# Motherboard_STM32F405RG_r1.net
KiCad netlist of a schematic drawn in EAGLE
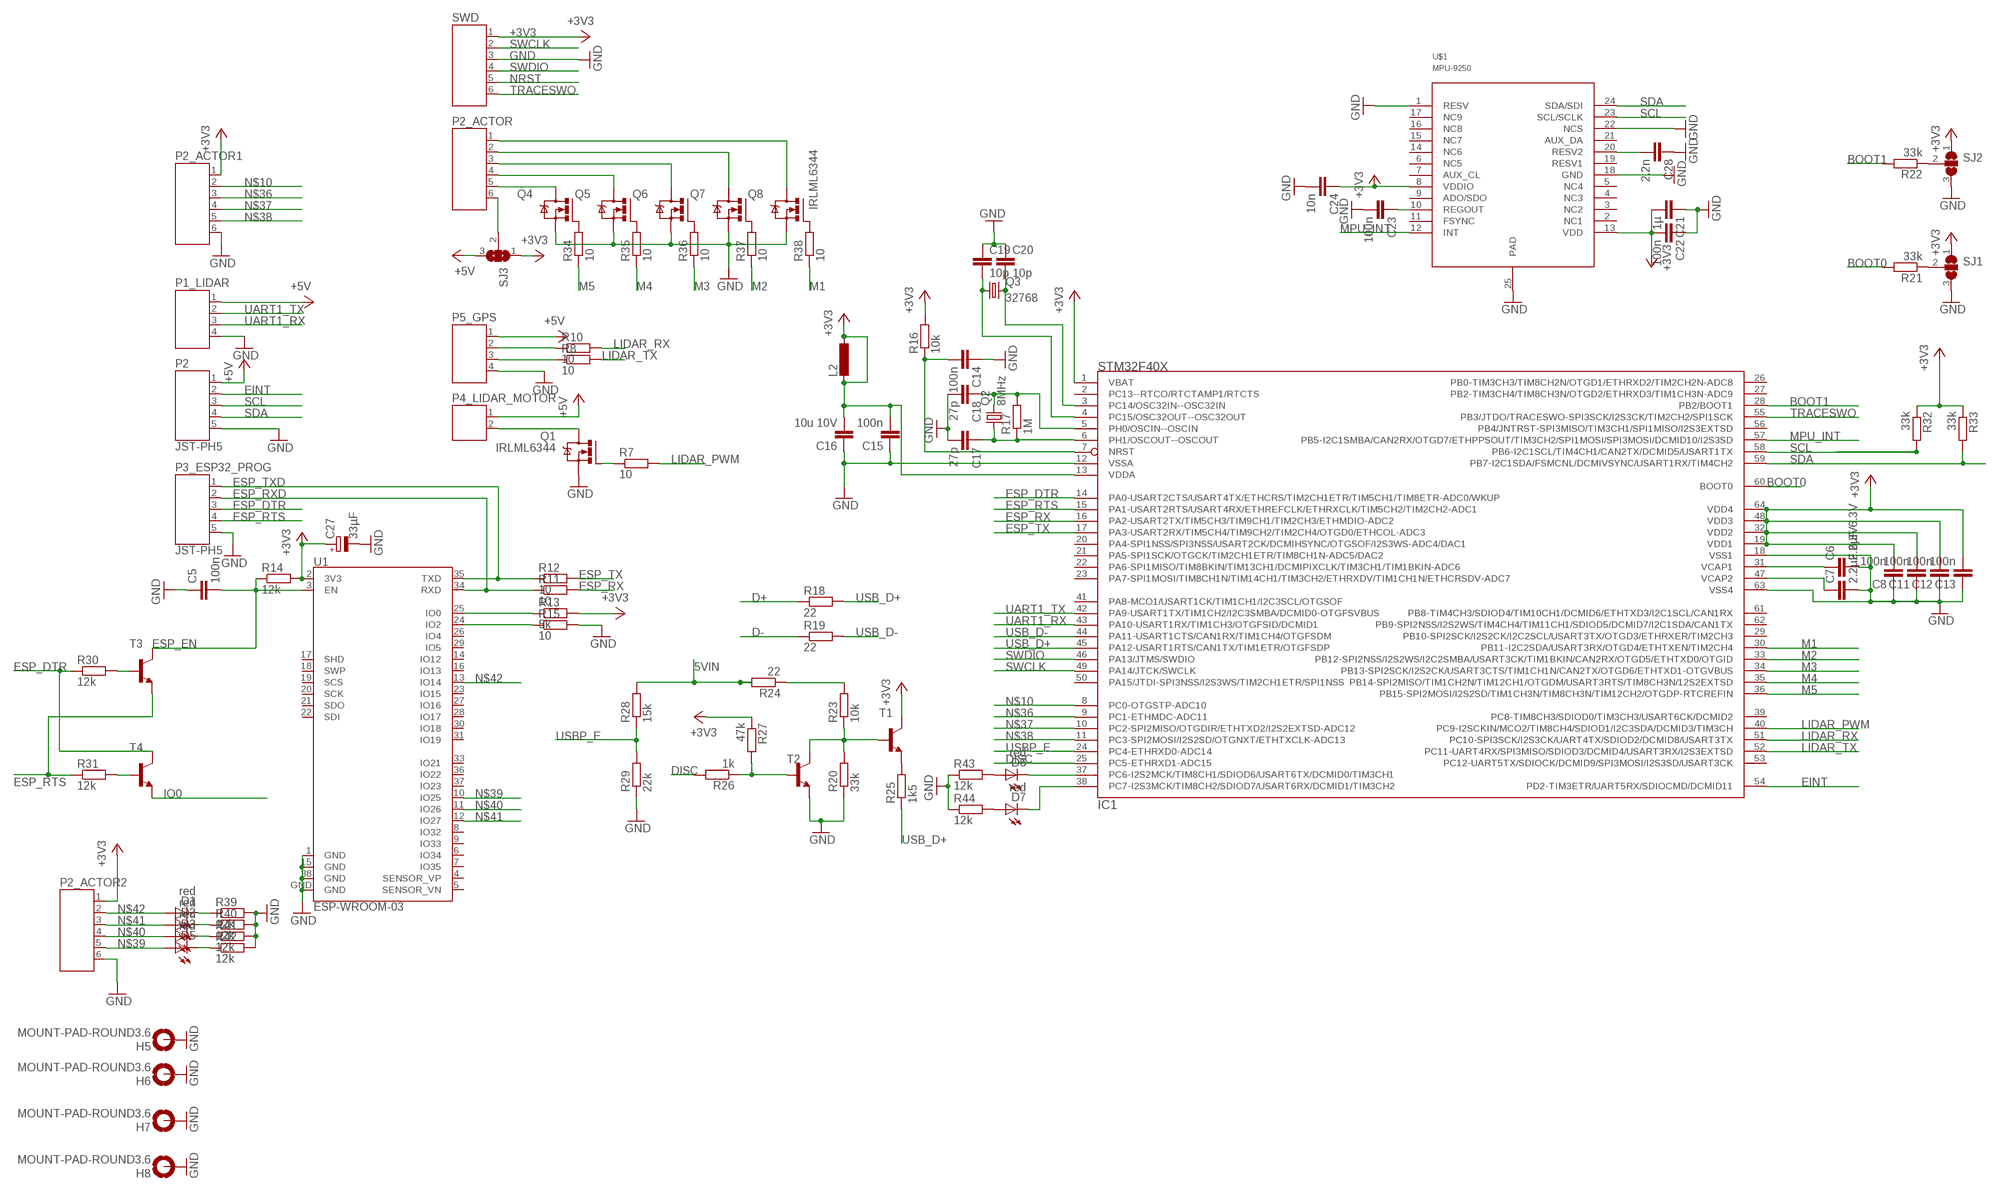
[diagram p0: schematic, sheet 1]
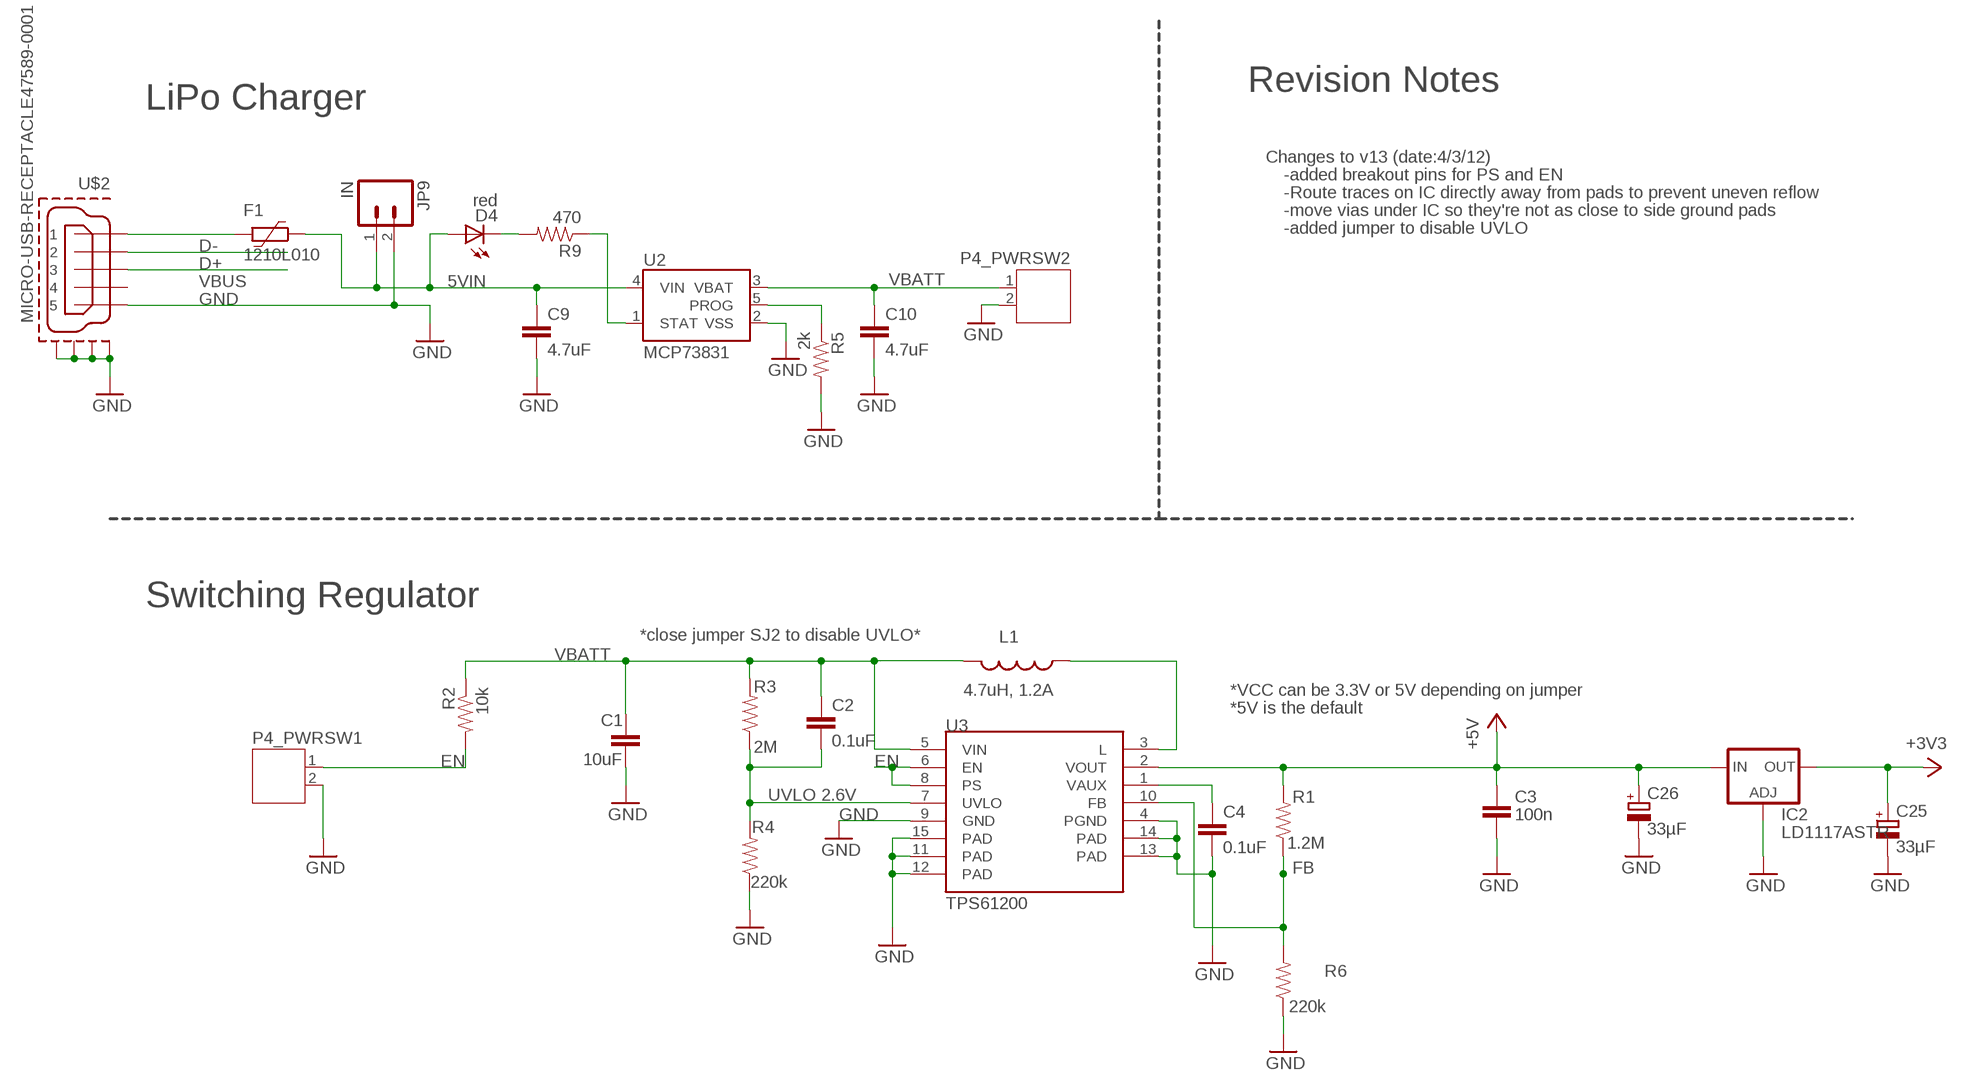
[diagram p1: schematic, sheet 2]

(export (version "E")
  (design (tool "Eeschema 10.0.6"))
  (components
    (comp (ref "C1")
      (value "10uF")
      (footprint "eagle-import:1206")
      (fields (field (name "MF") "KEMET") (field (name "MPN") "C1206C106K8RACTU"))
      (libsource (lib "eagle-import") (part "CAP1206"))
    )
    (comp (ref "C2")
      (value "0.1uF")
      (footprint "eagle-import:0603-CAP")
      (fields (field (name "MF") "YAGEO (PHYCOMP)") (field (name "MPN") "CC0603MRY5V9BB104"))
      (libsource (lib "eagle-import") (part "CAP0603-CAP"))
    )
    (comp (ref "C3")
      (value "100n")
      (footprint "eagle-import:0805")
      (fields (field (name "MF") "KEMET") (field (name "MPN") "C0603C104K5RACTU"))
      (libsource (lib "eagle-import") (part "CAP0805"))
    )
    (comp (ref "C4")
      (value "0.1uF")
      (footprint "eagle-import:0603-CAP")
      (fields (field (name "MF") "YAGEO (PHYCOMP)") (field (name "MPN") "CC0603MRY5V9BB104"))
      (libsource (lib "eagle-import") (part "CAP0603-CAP"))
    )
    (comp (ref "C9")
      (value "4.7uF")
      (footprint "eagle-import:0603-CAP")
      (fields (field (name "MF") "KEMET") (field (name "MPN") "C0603C475K8PACTU"))
      (libsource (lib "eagle-import") (part "CAP0603-CAP"))
    )
    (comp (ref "C10")
      (value "4.7uF")
      (footprint "eagle-import:0603-CAP")
      (fields (field (name "MF") "KEMET") (field (name "MPN") "C0603C475K8PACTU"))
      (libsource (lib "eagle-import") (part "CAP0603-CAP"))
    )
    (comp (ref "C25")
      (value "33µF")
      (footprint "eagle-import:A_3216-18W")
      (fields (field (name "MF") "AVX") (field (name "MPN") "TPSA336M006R0600"))
      (libsource (lib "eagle-import") (part "CPOL-EUA/3216-18W"))
    )
    (comp (ref "C26")
      (value "33µF")
      (footprint "eagle-import:A_3216-18W")
      (fields (field (name "MF") "AVX") (field (name "MPN") "TPSA336M006R0600"))
      (libsource (lib "eagle-import") (part "CPOL-EUA/3216-18W"))
    )
    (comp (ref "D4")
      (value "red")
      (footprint "eagle-import:LED-0603")
      (fields (field (name "MF") "OSRAM") (field (name "MPN") "LSQ976-Z"))
      (libsource (lib "eagle-import") (part "LED0603"))
    )
    (comp (ref "F1")
      (value "1210L010")
      (footprint "eagle-import:1210L")
      (fields
        (field (name "MF") "Littelfuse")
        (field (name "MF_1") "LITTELFUSE")
        (field (name "MPN") "1210L010WR")
      )
      (libsource (lib "eagle-import") (part "?1210L010"))
    )
    (comp (ref "IC2")
      (value "LD1117ASTR")
      (footprint "eagle-import:SOT223")
      (fields (field (name "MF") "ON SEMICONDUCTOR") (field (name "MPN") "NCP1117ST33T3G"))
      (libsource (lib "eagle-import") (part "LD117A?STR"))
    )
    (comp (ref "JP9")
      (value "IN")
      (footprint "eagle-import:1X02")
      (fields
        (field (name "MF") "JST (JAPAN SOLDERLESS TERMINALS)")
        (field (name "MPN") "B2B-PH-K-S(LF)(SN)")
      )
      (libsource (lib "eagle-import") (part "M02PTH"))
    )
    (comp (ref "L1")
      (value "4.7uH, 1.2A")
      (footprint "eagle-import:CDRH2D09")
      (fields (field (name "MF") "MURATA") (field (name "MPN") "LQH3NPN4R7MJ0L"))
      (libsource (lib "eagle-import") (part "INDUCTOR."))
    )
    (comp (ref "P4_PWRSW1")
      (value "JST-PH2")
      (footprint "eagle-import:JST-PH2")
      (fields
        (field (name "MF") "JST (JAPAN SOLDERLESS TERMINALS)")
        (field (name "MPN") "B2B-PH-K-S(LF)(SN)")
      )
      (libsource (lib "eagle-import") (part "JST-PH2"))
    )
    (comp (ref "P4_PWRSW2")
      (value "JST-PH2")
      (footprint "eagle-import:JST-PH2")
      (fields
        (field (name "MF") "JST (JAPAN SOLDERLESS TERMINALS)")
        (field (name "MPN") "B2B-PH-K-S(LF)(SN)")
      )
      (libsource (lib "eagle-import") (part "JST-PH2"))
    )
    (comp (ref "R1")
      (value "1.2M")
      (footprint "eagle-import:0603-RES")
      (fields (field (name "MF") "MULTICOMP") (field (name "MPN") "MCMR06W2004FTL"))
      (libsource (lib "eagle-import") (part "RESISTOR0603-RES"))
    )
    (comp (ref "R2")
      (value "10k")
      (footprint "eagle-import:0603-RES")
      (fields (field (name "MF") "MULTICOMP") (field (name "MPN") "MCMR06X1002FTL"))
      (libsource (lib "eagle-import") (part "RESISTOR0603-RES"))
    )
    (comp (ref "R3")
      (value "2M")
      (footprint "eagle-import:0603-RES")
      (fields (field (name "MF") "KOA SPEER ELECTRONICS") (field (name "MPN") "RK73H1JTTD1204F"))
      (libsource (lib "eagle-import") (part "RESISTOR0603-RES"))
    )
    (comp (ref "R4")
      (value "220k")
      (footprint "eagle-import:0603-RES")
      (fields (field (name "MF") "MULTICOMP") (field (name "MPN") "MCHP03W8F2203T5E"))
      (libsource (lib "eagle-import") (part "RESISTOR0603-RES"))
    )
    (comp (ref "R5")
      (value "2k")
      (footprint "eagle-import:0603-RES")
      (fields (field (name "MF") "YAGEO (PHYCOMP)") (field (name "MPN") "RC0603FR-072K2L."))
      (libsource (lib "eagle-import") (part "RESISTOR0603-RES"))
    )
    (comp (ref "R6")
      (value "220k")
      (footprint "eagle-import:0603-RES")
      (fields (field (name "MF") "MULTICOMP") (field (name "MPN") "MCHP03W8F2203T5E"))
      (libsource (lib "eagle-import") (part "RESISTOR0603-RES"))
    )
    (comp (ref "R9")
      (value "470")
      (footprint "eagle-import:0603-RES")
      (fields (field (name "MF") "MULTICOMP") (field (name "MPN") "MCHP03W8F4700T5E"))
      (libsource (lib "eagle-import") (part "RESISTOR0603-RES"))
    )
    (comp (ref "U$2")
      (value "MICRO-USB-RECEPTACLE47589-0001")
      (footprint "eagle-import:47589-0001")
      (fields (field (name "MF") "MOLEX") (field (name "MPN") "47589-0001"))
      (libsource (lib "eagle-import") (part "MICRO-USB-RECEPTACLE47589-0001"))
    )
    (comp (ref "U2")
      (value "MCP73831")
      (footprint "eagle-import:SOT23-5")
      (fields (field (name "MF") "MICROCHIP") (field (name "MPN") "MCP73831T-2ACI/OT"))
      (libsource (lib "eagle-import") (part "MCP73831"))
    )
    (comp (ref "U3")
      (value "TPS61200")
      (footprint "eagle-import:QFN-10_PAD")
      (fields (field (name "MF") "TEXAS INSTRUMENTS") (field (name "MPN") "TPS61200DRCT"))
      (libsource (lib "eagle-import") (part "TPS61200"))
    )
    (comp (ref "C5")
      (value "100n")
      (footprint "eagle-import:C0603")
      (fields (field (name "MF") "KEMET") (field (name "MPN") "C0603C104K5RACTU"))
      (libsource (lib "eagle-import") (part "C-EUC0603"))
    )
    (comp (ref "C6")
      (value "2.2µF 6.3V")
      (footprint "eagle-import:C0603")
      (fields (field (name "MF") "KEMET") (field (name "MPN") "C0603C225K9PACTU"))
      (libsource (lib "eagle-import") (part "C-EUC0603"))
    )
    (comp (ref "C7")
      (value "2.2µF 6.3V")
      (footprint "eagle-import:C0603")
      (fields (field (name "MF") "KEMET") (field (name "MPN") "C0603C225K9PACTU"))
      (libsource (lib "eagle-import") (part "C-EUC0603"))
    )
    (comp (ref "C8")
      (value "100n")
      (footprint "eagle-import:C0603")
      (fields (field (name "MF") "KEMET") (field (name "MPN") "C0603C104K5RACTU"))
      (libsource (lib "eagle-import") (part "C-EUC0603"))
    )
    (comp (ref "C11")
      (value "100n")
      (footprint "eagle-import:C0603")
      (fields (field (name "MF") "KEMET") (field (name "MPN") "C0603C104K5RACTU"))
      (libsource (lib "eagle-import") (part "C-EUC0603"))
    )
    (comp (ref "C12")
      (value "100n")
      (footprint "eagle-import:C0603")
      (fields (field (name "MF") "KEMET") (field (name "MPN") "C0603C104K5RACTU"))
      (libsource (lib "eagle-import") (part "C-EUC0603"))
    )
    (comp (ref "C13")
      (value "100n")
      (footprint "eagle-import:C0603")
      (fields (field (name "MF") "KEMET") (field (name "MPN") "C0603C104K5RACTU"))
      (libsource (lib "eagle-import") (part "C-EUC0603"))
    )
    (comp (ref "C14")
      (value "100n")
      (footprint "eagle-import:C0603")
      (fields (field (name "MF") "KEMET") (field (name "MPN") "C0603C104K5RACTU"))
      (libsource (lib "eagle-import") (part "C-EUC0603"))
    )
    (comp (ref "C15")
      (value "100n")
      (footprint "eagle-import:C0603")
      (fields (field (name "MF") "KEMET") (field (name "MPN") "C0603C104K5RACTU"))
      (libsource (lib "eagle-import") (part "C-EUC0603"))
    )
    (comp (ref "C16")
      (value "10u 10V")
      (footprint "eagle-import:C1206")
      (fields (field (name "MF") "KEMET") (field (name "MPN") "C1206C106K8RACTU"))
      (libsource (lib "eagle-import") (part "C-EUC1206"))
    )
    (comp (ref "C17")
      (value "27p")
      (footprint "eagle-import:C0603")
      (fields (field (name "MF") "YAGEO (PHYCOMP)") (field (name "MPN") "CC0603JRNPO9BN270"))
      (libsource (lib "eagle-import") (part "C-EUC0603"))
    )
    (comp (ref "C18")
      (value "27p")
      (footprint "eagle-import:C0603")
      (fields (field (name "MF") "YAGEO (PHYCOMP)") (field (name "MPN") "CC0603JRNPO9BN270"))
      (libsource (lib "eagle-import") (part "C-EUC0603"))
    )
    (comp (ref "C19")
      (value "10p")
      (footprint "eagle-import:C0603")
      (fields (field (name "MF") "AVX") (field (name "MPN") "06035A102JAT2A"))
      (libsource (lib "eagle-import") (part "C-EUC0603"))
    )
    (comp (ref "C20")
      (value "10p")
      (footprint "eagle-import:C0603")
      (fields (field (name "MF") "AVX") (field (name "MPN") "06035A102JAT2A"))
      (libsource (lib "eagle-import") (part "C-EUC0603"))
    )
    (comp (ref "C21")
      (value "1µ")
      (footprint "eagle-import:C0603")
      (fields (field (name "MF") "AVX") (field (name "MPN") "0603YC105KAT2A"))
      (libsource (lib "eagle-import") (part "C-EUC0603"))
    )
    (comp (ref "C22")
      (value "100n")
      (footprint "eagle-import:C0603")
      (fields (field (name "MF") "KEMET") (field (name "MPN") "C0603C104K5RACTU"))
      (libsource (lib "eagle-import") (part "C-EUC0603"))
    )
    (comp (ref "C23")
      (value "100n")
      (footprint "eagle-import:C0603")
      (fields (field (name "MF") "KEMET") (field (name "MPN") "C0603C104K5RACTU"))
      (libsource (lib "eagle-import") (part "C-EUC0603"))
    )
    (comp (ref "C24")
      (value "10n")
      (footprint "eagle-import:C0603")
      (fields (field (name "MF") "YAGEO (PHYCOMP)") (field (name "MPN") "CC0603KRX7R9BB103"))
      (libsource (lib "eagle-import") (part "C-EUC0603"))
    )
    (comp (ref "C27")
      (value "33µF")
      (footprint "eagle-import:A_3216-18W")
      (fields (field (name "MF") "AVX") (field (name "MPN") "TPSA336M006R0600"))
      (libsource (lib "eagle-import") (part "CPOL-EUA/3216-18W"))
    )
    (comp (ref "C28")
      (value "2.2n")
      (footprint "eagle-import:C0603")
      (fields (field (name "MF") "YAGEO (PHYCOMP)") (field (name "MPN") "CC0603KRX7R9BB222"))
      (libsource (lib "eagle-import") (part "C-EUC0603"))
    )
    (comp (ref "D1")
      (value "red")
      (footprint "eagle-import:LED-0603")
      (fields (field (name "MF") "OSRAM") (field (name "MPN") "LSQ976-Z"))
      (libsource (lib "eagle-import") (part "LED0603"))
    )
    (comp (ref "D2")
      (value "red")
      (footprint "eagle-import:LED-0603")
      (fields (field (name "MF") "OSRAM") (field (name "MPN") "LSQ976-Z"))
      (libsource (lib "eagle-import") (part "LED0603"))
    )
    (comp (ref "D3")
      (value "red")
      (footprint "eagle-import:LED-0603")
      (fields (field (name "MF") "OSRAM") (field (name "MPN") "LSQ976-Z"))
      (libsource (lib "eagle-import") (part "LED0603"))
    )
    (comp (ref "D5")
      (value "red")
      (footprint "eagle-import:LED-0603")
      (fields (field (name "MF") "OSRAM") (field (name "MPN") "LSQ976-Z"))
      (libsource (lib "eagle-import") (part "LED0603"))
    )
    (comp (ref "D6")
      (value "red")
      (footprint "eagle-import:LED-0603")
      (fields (field (name "MF") "OSRAM") (field (name "MPN") "LSQ976-Z"))
      (libsource (lib "eagle-import") (part "LED0603"))
    )
    (comp (ref "D7")
      (value "red")
      (footprint "eagle-import:LED-0603")
      (fields (field (name "MF") "OSRAM") (field (name "MPN") "LSQ976-Z"))
      (libsource (lib "eagle-import") (part "LED0603"))
    )
    (comp (ref "H5")
      (value "MOUNT-PAD-ROUND3.6")
      (footprint "eagle-import:3,6-PAD")
      (libsource (lib "eagle-import") (part "MOUNT-PAD-ROUND3.6"))
    )
    (comp (ref "H6")
      (value "MOUNT-PAD-ROUND3.6")
      (footprint "eagle-import:3,6-PAD")
      (libsource (lib "eagle-import") (part "MOUNT-PAD-ROUND3.6"))
    )
    (comp (ref "H7")
      (value "MOUNT-PAD-ROUND3.6")
      (footprint "eagle-import:3,6-PAD")
      (libsource (lib "eagle-import") (part "MOUNT-PAD-ROUND3.6"))
    )
    (comp (ref "H8")
      (value "MOUNT-PAD-ROUND3.6")
      (footprint "eagle-import:3,6-PAD")
      (libsource (lib "eagle-import") (part "MOUNT-PAD-ROUND3.6"))
    )
    (comp (ref "IC1")
      (value "STM32F40X")
      (footprint "eagle-import:LQFP64")
      (fields (field (name "MF") "STMICROELECTRONICS") (field (name "MPN") "STM32F405RGT6"))
      (libsource (lib "eagle-import") (part "STM32F40X"))
    )
    (comp (ref "L2")
      (value "L-EUL1812")
      (footprint "eagle-import:L1812")
      (libsource (lib "eagle-import") (part "L-EUL1812"))
    )
    (comp (ref "P1_LIDAR")
      (value "JST-PH4")
      (footprint "eagle-import:JST-PH4")
      (fields
        (field (name "MF") "JST (JAPAN SOLDERLESS TERMINALS)")
        (field (name "MPN") "B4B-PH-K-S(LF)(SN)")
      )
      (libsource (lib "eagle-import") (part "JST-PH4"))
    )
    (comp (ref "P2")
      (value "JST-PH5")
      (footprint "eagle-import:JST-PH5")
      (fields
        (field (name "MF") "JST (JAPAN SOLDERLESS TERMINALS)")
        (field (name "MPN") "B5B-PH-K-S(LF)(SN)")
      )
      (libsource (lib "eagle-import") (part "JST-PH5"))
    )
    (comp (ref "P2_ACTOR")
      (value "JST-PH6")
      (footprint "eagle-import:JST-PH6")
      (fields
        (field (name "MF") "JST (JAPAN SOLDERLESS TERMINALS)")
        (field (name "MPN") "B6B-PH-K-S(LF)(SN)")
      )
      (libsource (lib "eagle-import") (part "JST-PH6"))
    )
    (comp (ref "P2_ACTOR1")
      (value "JST-PH6")
      (footprint "eagle-import:JST-PH6")
      (fields
        (field (name "MF") "JST (JAPAN SOLDERLESS TERMINALS)")
        (field (name "MPN") "B6B-PH-K-S(LF)(SN)")
      )
      (libsource (lib "eagle-import") (part "JST-PH6"))
    )
    (comp (ref "P2_ACTOR2")
      (value "JST-PH6")
      (footprint "eagle-import:JST-PH6")
      (fields
        (field (name "MF") "JST (JAPAN SOLDERLESS TERMINALS)")
        (field (name "MPN") "B6B-PH-K-S(LF)(SN)")
      )
      (libsource (lib "eagle-import") (part "JST-PH6"))
    )
    (comp (ref "P3_ESP32_PROG")
      (value "JST-PH5")
      (footprint "eagle-import:JST-PH5")
      (fields
        (field (name "MF") "JST (JAPAN SOLDERLESS TERMINALS)")
        (field (name "MPN") "B5B-PH-K-S(LF)(SN)")
      )
      (libsource (lib "eagle-import") (part "JST-PH5"))
    )
    (comp (ref "P4_LIDAR_MOTOR")
      (value "JST-PH2")
      (footprint "eagle-import:JST-PH2")
      (fields
        (field (name "MF") "JST (JAPAN SOLDERLESS TERMINALS)")
        (field (name "MPN") "B2B-PH-K-S(LF)(SN)")
      )
      (libsource (lib "eagle-import") (part "JST-PH2"))
    )
    (comp (ref "P5_GPS")
      (value "JST-PH4")
      (footprint "eagle-import:JST-PH4")
      (fields
        (field (name "MF") "JST (JAPAN SOLDERLESS TERMINALS)")
        (field (name "MPN") "B4B-PH-K-S(LF)(SN)")
      )
      (libsource (lib "eagle-import") (part "JST-PH4"))
    )
    (comp (ref "Q1")
      (value "IRLML6344")
      (footprint "eagle-import:SOT23")
      (fields (field (name "MF") "INFINEON") (field (name "MPN") "IRLML6344TRPBF"))
      (libsource (lib "eagle-import") (part "IRLML6344"))
    )
    (comp (ref "Q2")
      (value "8MHz")
      (footprint "eagle-import:HC18U-V")
      (fields
        (field (name "MF") "MULTICOMP")
        (field (name "MPN") "HC49S-8-30-50-70-30-ATF")
        (field (name "OC_FARNELL") "1666997")
      )
      (libsource (lib "eagle-import") (part "CRYSTALHC18U-V"))
    )
    (comp (ref "Q3")
      (value "32768")
      (footprint "eagle-import:TC38H")
      (fields
        (field (name "MF") "CITIZEN FINETECH MIYOTA")
        (field (name "MPN") "CFS206 32.768KDZB-UB")
        (field (name "OC_FARNELL") "1457085")
      )
      (libsource (lib "eagle-import") (part "CRYSTALTC38H"))
    )
    (comp (ref "Q4")
      (value "IRLML6344")
      (footprint "eagle-import:SOT23")
      (fields (field (name "MF") "INFINEON") (field (name "MPN") "IRLML6344TRPBF"))
      (libsource (lib "eagle-import") (part "IRLML6344"))
    )
    (comp (ref "Q5")
      (value "IRLML6344")
      (footprint "eagle-import:SOT23")
      (fields (field (name "MF") "INFINEON") (field (name "MPN") "IRLML6344TRPBF"))
      (libsource (lib "eagle-import") (part "IRLML6344"))
    )
    (comp (ref "Q6")
      (value "IRLML6344")
      (footprint "eagle-import:SOT23")
      (fields (field (name "MF") "INFINEON") (field (name "MPN") "IRLML6344TRPBF"))
      (libsource (lib "eagle-import") (part "IRLML6344"))
    )
    (comp (ref "Q7")
      (value "IRLML6344")
      (footprint "eagle-import:SOT23")
      (fields (field (name "MF") "INFINEON") (field (name "MPN") "IRLML6344TRPBF"))
      (libsource (lib "eagle-import") (part "IRLML6344"))
    )
    (comp (ref "Q8")
      (value "IRLML6344")
      (footprint "eagle-import:SOT23")
      (fields (field (name "MF") "INFINEON") (field (name "MPN") "IRLML6344TRPBF"))
      (libsource (lib "eagle-import") (part "IRLML6344"))
    )
    (comp (ref "R7")
      (value "10")
      (footprint "eagle-import:R0603")
      (fields (field (name "MF") "VISHAY") (field (name "MPN") "CRCW060310R0FKEA"))
      (libsource (lib "eagle-import") (part "R-EU_R0603"))
    )
    (comp (ref "R8")
      (value "10")
      (footprint "eagle-import:R0603")
      (fields (field (name "MF") "VISHAY") (field (name "MPN") "CRCW060310R0FKEA"))
      (libsource (lib "eagle-import") (part "R-EU_R0603"))
    )
    (comp (ref "R10")
      (value "10")
      (footprint "eagle-import:R0603")
      (fields (field (name "MF") "VISHAY") (field (name "MPN") "CRCW060310R0FKEA"))
      (libsource (lib "eagle-import") (part "R-EU_R0603"))
    )
    (comp (ref "R11")
      (value "10")
      (footprint "eagle-import:R0603")
      (fields (field (name "MF") "VISHAY") (field (name "MPN") "CRCW060310R0FKEA"))
      (libsource (lib "eagle-import") (part "R-EU_R0603"))
    )
    (comp (ref "R12")
      (value "10")
      (footprint "eagle-import:R0603")
      (fields (field (name "MF") "VISHAY") (field (name "MPN") "CRCW060310R0FKEA"))
      (libsource (lib "eagle-import") (part "R-EU_R0603"))
    )
    (comp (ref "R13")
      (value "5k")
      (footprint "eagle-import:R0603")
      (fields (field (name "MF") "VISHAY") (field (name "MPN") "CRCW060310R0FKEA"))
      (libsource (lib "eagle-import") (part "R-EU_R0603"))
    )
    (comp (ref "R14")
      (value "12k")
      (footprint "eagle-import:R0603")
      (fields (field (name "MF") "VISHAY") (field (name "MPN") "CRCW060310R0FKEA"))
      (libsource (lib "eagle-import") (part "R-EU_R0603"))
    )
    (comp (ref "R15")
      (value "10")
      (footprint "eagle-import:R0603")
      (fields (field (name "MF") "VISHAY") (field (name "MPN") "CRCW060310R0FKEA"))
      (libsource (lib "eagle-import") (part "R-EU_R0603"))
    )
    (comp (ref "R16")
      (value "10k")
      (footprint "eagle-import:R0603")
      (fields (field (name "MF") "VISHAY") (field (name "MPN") "CRCW060310R0FKEA"))
      (libsource (lib "eagle-import") (part "R-EU_R0603"))
    )
    (comp (ref "R17")
      (value "1M")
      (footprint "eagle-import:R0603")
      (fields (field (name "MF") "VISHAY") (field (name "MPN") "CRCW06031M00FKEA"))
      (libsource (lib "eagle-import") (part "R-EU_R0603"))
    )
    (comp (ref "R18")
      (value "22")
      (footprint "eagle-import:R0603")
      (fields (field (name "MF") "VISHAY") (field (name "MPN") "CRCW060322R0FKEA"))
      (libsource (lib "eagle-import") (part "R-EU_R0603"))
    )
    (comp (ref "R19")
      (value "22")
      (footprint "eagle-import:R0603")
      (fields (field (name "MF") "VISHAY") (field (name "MPN") "CRCW060322R0FKEA"))
      (libsource (lib "eagle-import") (part "R-EU_R0603"))
    )
    (comp (ref "R20")
      (value "33k")
      (footprint "eagle-import:R0603")
      (fields (field (name "MF") "VISHAY") (field (name "MPN") "CRCW060333K0FKEA"))
      (libsource (lib "eagle-import") (part "R-EU_R0603"))
    )
    (comp (ref "R21")
      (value "33k")
      (footprint "eagle-import:R0603")
      (fields (field (name "MF") "VISHAY") (field (name "MPN") "CRCW060333K0FKEA"))
      (libsource (lib "eagle-import") (part "R-EU_R0603"))
    )
    (comp (ref "R22")
      (value "33k")
      (footprint "eagle-import:R0603")
      (fields (field (name "MF") "VISHAY") (field (name "MPN") "CRCW060333K0FKEA"))
      (libsource (lib "eagle-import") (part "R-EU_R0603"))
    )
    (comp (ref "R23")
      (value "10k")
      (footprint "eagle-import:R0603")
      (fields (field (name "MF") "MULTICOMP") (field (name "MPN") "MCMR06X1002FTL"))
      (libsource (lib "eagle-import") (part "R-EU_R0603"))
    )
    (comp (ref "R24")
      (value "22")
      (footprint "eagle-import:R0603")
      (fields (field (name "MF") "VISHAY") (field (name "MPN") "CRCW060322R0FKEA"))
      (libsource (lib "eagle-import") (part "R-EU_R0603"))
    )
    (comp (ref "R25")
      (value "1k5")
      (footprint "eagle-import:R0603")
      (fields (field (name "MF") "MULTICOMP") (field (name "MPN") "MCMR06X1501FTL"))
      (libsource (lib "eagle-import") (part "R-EU_R0603"))
    )
    (comp (ref "R26")
      (value "1k")
      (footprint "eagle-import:R0603")
      (fields (field (name "MF") "VISHAY") (field (name "MPN") "CRCW06031K00FKEA"))
      (libsource (lib "eagle-import") (part "R-EU_R0603"))
    )
    (comp (ref "R27")
      (value "47k")
      (footprint "eagle-import:R0603")
      (fields (field (name "MF") "VISHAY") (field (name "MPN") "CRCW060347K0FKEA"))
      (libsource (lib "eagle-import") (part "R-EU_R0603"))
    )
    (comp (ref "R28")
      (value "15k")
      (footprint "eagle-import:R0603")
      (fields (field (name "MF") "VISHAY") (field (name "MPN") "CRCW060315K0FKEA"))
      (libsource (lib "eagle-import") (part "R-EU_R0603"))
    )
    (comp (ref "R29")
      (value "22k")
      (footprint "eagle-import:R0603")
      (fields (field (name "MF") "TE CONNECTIVITY / NEOHM") (field (name "MPN") "CPF0603F4K22C1"))
      (libsource (lib "eagle-import") (part "R-EU_R0603"))
    )
    (comp (ref "R30")
      (value "12k")
      (footprint "eagle-import:R0603")
      (fields (field (name "MF") "MULTICOMP") (field (name "MPN") "MC0063W060312K8"))
      (libsource (lib "eagle-import") (part "R-EU_R0603"))
    )
    (comp (ref "R31")
      (value "12k")
      (footprint "eagle-import:R0603")
      (fields (field (name "MF") "MULTICOMP") (field (name "MPN") "MC0063W060312K8"))
      (libsource (lib "eagle-import") (part "R-EU_R0603"))
    )
    (comp (ref "R32")
      (value "33k")
      (footprint "eagle-import:R0603")
      (fields (field (name "MF") "VISHAY") (field (name "MPN") "CRCW060333K0FKEA"))
      (libsource (lib "eagle-import") (part "R-EU_R0603"))
    )
    (comp (ref "R33")
      (value "33k")
      (footprint "eagle-import:R0603")
      (fields (field (name "MF") "VISHAY") (field (name "MPN") "CRCW060333K0FKEA"))
      (libsource (lib "eagle-import") (part "R-EU_R0603"))
    )
    (comp (ref "R34")
      (value "10")
      (footprint "eagle-import:R0603")
      (fields (field (name "MF") "VISHAY") (field (name "MPN") "CRCW060310R0FKEA"))
      (libsource (lib "eagle-import") (part "R-EU_R0603"))
    )
    (comp (ref "R35")
      (value "10")
      (footprint "eagle-import:R0603")
      (fields (field (name "MF") "VISHAY") (field (name "MPN") "CRCW060310R0FKEA"))
      (libsource (lib "eagle-import") (part "R-EU_R0603"))
    )
    (comp (ref "R36")
      (value "10")
      (footprint "eagle-import:R0603")
      (fields (field (name "MF") "VISHAY") (field (name "MPN") "CRCW060310R0FKEA"))
      (libsource (lib "eagle-import") (part "R-EU_R0603"))
    )
    (comp (ref "R37")
      (value "10")
      (footprint "eagle-import:R0603")
      (fields (field (name "MF") "VISHAY") (field (name "MPN") "CRCW060310R0FKEA"))
      (libsource (lib "eagle-import") (part "R-EU_R0603"))
    )
    (comp (ref "R38")
      (value "10")
      (footprint "eagle-import:R0603")
      (fields (field (name "MF") "VISHAY") (field (name "MPN") "CRCW060310R0FKEA"))
      (libsource (lib "eagle-import") (part "R-EU_R0603"))
    )
    (comp (ref "R39")
      (value "12k")
      (footprint "eagle-import:R0603")
      (fields (field (name "MF") "MULTICOMP") (field (name "MPN") "MC0063W060312K8"))
      (libsource (lib "eagle-import") (part "R-EU_R0603"))
    )
    (comp (ref "R40")
      (value "12k")
      (footprint "eagle-import:R0603")
      (fields (field (name "MF") "MULTICOMP") (field (name "MPN") "MC0063W060312K8"))
      (libsource (lib "eagle-import") (part "R-EU_R0603"))
    )
    (comp (ref "R41")
      (value "12k")
      (footprint "eagle-import:R0603")
      (fields (field (name "MF") "MULTICOMP") (field (name "MPN") "MC0063W060312K8"))
      (libsource (lib "eagle-import") (part "R-EU_R0603"))
    )
    (comp (ref "R42")
      (value "12k")
      (footprint "eagle-import:R0603")
      (fields (field (name "MF") "MULTICOMP") (field (name "MPN") "MC0063W060312K8"))
      (libsource (lib "eagle-import") (part "R-EU_R0603"))
    )
    (comp (ref "R43")
      (value "12k")
      (footprint "eagle-import:R0603")
      (fields (field (name "MF") "MULTICOMP") (field (name "MPN") "MC0063W060312K8"))
      (libsource (lib "eagle-import") (part "R-EU_R0603"))
    )
    (comp (ref "R44")
      (value "12k")
      (footprint "eagle-import:R0603")
      (fields (field (name "MF") "MULTICOMP") (field (name "MPN") "MC0063W060312K8"))
      (libsource (lib "eagle-import") (part "R-EU_R0603"))
    )
    (comp (ref "SJ1")
      (value "SJ2W")
      (footprint "eagle-import:SJ_2")
      (libsource (lib "eagle-import") (part "SJ2W"))
    )
    (comp (ref "SJ2")
      (value "SJ2W")
      (footprint "eagle-import:SJ_2")
      (libsource (lib "eagle-import") (part "SJ2W"))
    )
    (comp (ref "SJ3")
      (value "SJ2W")
      (footprint "eagle-import:SJ_2")
      (libsource (lib "eagle-import") (part "SJ2W"))
    )
    (comp (ref "SWD")
      (value "JST-PH6")
      (footprint "eagle-import:JST-PH6")
      (fields
        (field (name "MF") "JST (JAPAN SOLDERLESS TERMINALS)")
        (field (name "MPN") "B6B-PH-K-S(LF)(SN)")
      )
      (libsource (lib "eagle-import") (part "JST-PH6"))
    )
    (comp (ref "T1")
      (value "BC817-16-NPN-SOT23-BEC")
      (footprint "eagle-import:SOT23-BEC")
      (fields (field (name "MF") "NEXPERIA") (field (name "MPN") "BC817,215"))
      (libsource (lib "eagle-import") (part "-NPN-SOT23-BECBC817-16"))
    )
    (comp (ref "T2")
      (value "BC817-16-NPN-SOT23-BEC")
      (footprint "eagle-import:SOT23-BEC")
      (fields (field (name "MF") "NEXPERIA") (field (name "MPN") "BC817,215"))
      (libsource (lib "eagle-import") (part "-NPN-SOT23-BECBC817-16"))
    )
    (comp (ref "T3")
      (value "BC817-16-NPN-SOT23-BEC")
      (footprint "eagle-import:SOT23-BEC")
      (fields (field (name "MF") "NEXPERIA") (field (name "MPN") "BC817,215"))
      (libsource (lib "eagle-import") (part "-NPN-SOT23-BECBC817-16"))
    )
    (comp (ref "T4")
      (value "BC817-16-NPN-SOT23-BEC")
      (footprint "eagle-import:SOT23-BEC")
      (fields (field (name "MF") "NEXPERIA") (field (name "MPN") "BC817,215"))
      (libsource (lib "eagle-import") (part "-NPN-SOT23-BECBC817-16"))
    )
    (comp (ref "U$1")
      (value "MPU-9250")
      (footprint "eagle-import:LEAD-QFN24")
      (fields (field (name "MF") "INVENSENSE") (field (name "MPN") "MPU-6050"))
      (libsource (lib "eagle-import") (part "MPU-9250"))
    )
    (comp (ref "U1")
      (value "ESP-WROOM-03")
      (footprint "eagle-import:ESP-WROOM-03")
      (libsource (lib "eagle-import") (part "ESP-WROOM-03"))
    )
  )
  (nets
    (net (code "1") (name "+3V3") (class "Default")
      (node (ref "C11") (pin "2") (pinfunction "2_2") (pintype "passive"))
      (node (ref "C12") (pin "2") (pinfunction "2_2") (pintype "passive"))
      (node (ref "C13") (pin "2") (pinfunction "2_2") (pintype "passive"))
      (node (ref "C15") (pin "2") (pinfunction "2_2") (pintype "passive"))
      (node (ref "C16") (pin "2") (pinfunction "2_2") (pintype "passive"))
      (node (ref "C21") (pin "2") (pinfunction "2_2") (pintype "passive"))
      (node (ref "C22") (pin "2") (pinfunction "2_2") (pintype "passive"))
      (node (ref "C24") (pin "1") (pinfunction "1_1") (pintype "passive"))
      (node (ref "C25") (pin "+") (pinfunction "+_+") (pintype "passive"))
      (node (ref "C27") (pin "+") (pinfunction "+_+") (pintype "passive"))
      (node (ref "C8") (pin "2") (pinfunction "2_2") (pintype "passive"))
      (node (ref "IC1") (pin "1") (pinfunction "VBAT_1") (pintype "power_in"))
      (node (ref "IC1") (pin "13") (pinfunction "VDDA_13") (pintype "power_in"))
      (node (ref "IC1") (pin "19") (pinfunction "VDD1_19") (pintype "power_in"))
      (node (ref "IC1") (pin "32") (pinfunction "VDD2_32") (pintype "power_in"))
      (node (ref "IC1") (pin "48") (pinfunction "VDD3_48") (pintype "power_in"))
      (node (ref "IC1") (pin "64") (pinfunction "VDD4_64") (pintype "bidirectional"))
      (node (ref "IC2") (pin "2") (pinfunction "OUT_2") (pintype "passive"))
      (node (ref "IC2") (pin "4") (pinfunction "OUT_4") (pintype "passive"))
      (node (ref "L2") (pin "1") (pinfunction "1_1") (pintype "passive"))
      (node (ref "L2") (pin "2") (pinfunction "2_2") (pintype "passive"))
      (node (ref "P2_ACTOR1") (pin "1") (pinfunction "1_1") (pintype "passive"))
      (node (ref "P2_ACTOR2") (pin "1") (pinfunction "1_1") (pintype "passive"))
      (node (ref "R13") (pin "2") (pinfunction "2_2") (pintype "passive"))
      (node (ref "R14") (pin "2") (pinfunction "2_2") (pintype "passive"))
      (node (ref "R16") (pin "2") (pinfunction "2_2") (pintype "passive"))
      (node (ref "R27") (pin "1") (pinfunction "1_1") (pintype "passive"))
      (node (ref "R32") (pin "1") (pinfunction "1_1") (pintype "passive"))
      (node (ref "R33") (pin "1") (pinfunction "1_1") (pintype "passive"))
      (node (ref "SJ1") (pin "1") (pinfunction "1_1") (pintype "passive"))
      (node (ref "SJ2") (pin "1") (pinfunction "1_1") (pintype "passive"))
      (node (ref "SJ3") (pin "1") (pinfunction "1_1") (pintype "passive"))
      (node (ref "SWD") (pin "1") (pinfunction "1_1") (pintype "passive"))
      (node (ref "T1") (pin "C") (pinfunction "C_C") (pintype "passive"))
      (node (ref "U$1") (pin "13") (pinfunction "VDD_13") (pintype "bidirectional"))
      (node (ref "U$1") (pin "8") (pinfunction "VDDIO_8") (pintype "bidirectional"))
      (node (ref "U1") (pin "2") (pinfunction "3V3_2") (pintype "bidirectional"))
    )
    (net (code "2") (name "+5V") (class "Default")
      (node (ref "C26") (pin "+") (pinfunction "+_+") (pintype "passive"))
      (node (ref "C3") (pin "1") (pinfunction "1_1") (pintype "passive"))
      (node (ref "IC2") (pin "3") (pinfunction "IN_3") (pintype "input"))
      (node (ref "P1_LIDAR") (pin "1") (pinfunction "1_1") (pintype "passive"))
      (node (ref "P2") (pin "1") (pinfunction "1_1") (pintype "passive"))
      (node (ref "P4_LIDAR_MOTOR") (pin "1") (pinfunction "1_1") (pintype "passive"))
      (node (ref "P5_GPS") (pin "1") (pinfunction "1_1") (pintype "passive"))
      (node (ref "R1") (pin "2") (pinfunction "2_2") (pintype "passive"))
      (node (ref "SJ3") (pin "3") (pinfunction "3_3") (pintype "passive"))
      (node (ref "U3") (pin "2") (pinfunction "VOUT_2") (pintype "passive"))
    )
    (net (code "3") (name "5VIN") (class "Default")
      (node (ref "C9") (pin "1") (pinfunction "1_1") (pintype "passive"))
      (node (ref "D4") (pin "A") (pinfunction "A_A") (pintype "passive"))
      (node (ref "F1") (pin "1") (pinfunction "1_1") (pintype "passive"))
      (node (ref "JP9") (pin "1") (pinfunction "1_1") (pintype "passive"))
      (node (ref "R24") (pin "2") (pinfunction "2_2") (pintype "passive"))
      (node (ref "R28") (pin "2") (pinfunction "2_2") (pintype "passive"))
      (node (ref "U2") (pin "4") (pinfunction "VIN_4") (pintype "power_in"))
    )
    (net (code "4") (name "BOOT0") (class "Default")
      (node (ref "IC1") (pin "60") (pinfunction "BOOT0_60") (pintype "input"))
      (node (ref "R21") (pin "2") (pinfunction "2_2") (pintype "passive"))
    )
    (net (code "5") (name "BOOT1") (class "Default")
      (node (ref "IC1") (pin "28") (pinfunction "PB2/BOOT1_28") (pintype "bidirectional"))
      (node (ref "R22") (pin "2") (pinfunction "2_2") (pintype "passive"))
    )
    (net (code "6") (name "D+") (class "Default")
      (node (ref "R18") (pin "1") (pinfunction "1_1") (pintype "passive"))
      (node (ref "U$2") (pin "3") (pinfunction "3_3") (pintype "input"))
    )
    (net (code "7") (name "D-") (class "Default")
      (node (ref "R19") (pin "1") (pinfunction "1_1") (pintype "passive"))
      (node (ref "U$2") (pin "2") (pinfunction "2_2") (pintype "input"))
    )
    (net (code "8") (name "DISC") (class "Default")
      (node (ref "IC1") (pin "25") (pinfunction "PC5-ETHRXD1-ADC15_25") (pintype "bidirectional"))
      (node (ref "R26") (pin "2") (pinfunction "2_2") (pintype "passive"))
    )
    (net (code "9") (name "EINT") (class "Default")
      (node (ref "IC1") (pin "54") (pinfunction "PD2-TIM3ETR/UART5RX/SDIOCMD/DCMID11_54") (pintype "bidirectional"))
      (node (ref "P2") (pin "2") (pinfunction "2_2") (pintype "passive"))
    )
    (net (code "10") (name "EN") (class "Default")
      (node (ref "P4_PWRSW1") (pin "1") (pinfunction "1_1") (pintype "passive"))
      (node (ref "R2") (pin "2") (pinfunction "2_2") (pintype "passive"))
      (node (ref "U3") (pin "6") (pinfunction "EN_6") (pintype "input"))
      (node (ref "U3") (pin "8") (pinfunction "PS_8") (pintype "input"))
    )
    (net (code "11") (name "ESP_DTR") (class "Default")
      (node (ref "IC1") (pin "14") (pinfunction "PA0-USART2CTS/USART4TX/ETHCRS/TIM2CH1ETR/TIM5CH1/TIM8ETR-ADC0/WKUP_14") (pintype "bidirectional"))
      (node (ref "P3_ESP32_PROG") (pin "3") (pinfunction "3_3") (pintype "passive"))
      (node (ref "R30") (pin "1") (pinfunction "1_1") (pintype "passive"))
      (node (ref "T4") (pin "C") (pinfunction "C_C") (pintype "passive"))
    )
    (net (code "12") (name "ESP_EN") (class "Default")
      (node (ref "C5") (pin "2") (pinfunction "2_2") (pintype "passive"))
      (node (ref "R14") (pin "1") (pinfunction "1_1") (pintype "passive"))
      (node (ref "T3") (pin "C") (pinfunction "C_C") (pintype "passive"))
      (node (ref "U1") (pin "3") (pinfunction "EN_3") (pintype "bidirectional"))
    )
    (net (code "13") (name "ESP_RTS") (class "Default")
      (node (ref "IC1") (pin "15") (pinfunction "PA1-USART2RTS/USART4RX/ETHREFCLK/ETHRXCLK/TIM5CH2/TIM2CH2-ADC1_15") (pintype "bidirectional"))
      (node (ref "P3_ESP32_PROG") (pin "4") (pinfunction "4_4") (pintype "passive"))
      (node (ref "R31") (pin "1") (pinfunction "1_1") (pintype "passive"))
      (node (ref "T3") (pin "E") (pinfunction "E_E") (pintype "passive"))
    )
    (net (code "14") (name "ESP_RX") (class "Default")
      (node (ref "IC1") (pin "16") (pinfunction "PA2-USART2TX/TIM5CH3/TIM9CH1/TIM2CH3/ETHMDIO-ADC2_16") (pintype "bidirectional"))
      (node (ref "R11") (pin "2") (pinfunction "2_2") (pintype "passive"))
    )
    (net (code "15") (name "ESP_RXD") (class "Default")
      (node (ref "P3_ESP32_PROG") (pin "2") (pinfunction "2_2") (pintype "passive"))
      (node (ref "R11") (pin "1") (pinfunction "1_1") (pintype "passive"))
      (node (ref "U1") (pin "34") (pinfunction "RXD_34") (pintype "bidirectional"))
    )
    (net (code "16") (name "ESP_TX") (class "Default")
      (node (ref "IC1") (pin "17") (pinfunction "PA3-USART2RX/TIM5CH4/TIM9CH2/TIM2CH4/OTGD0/ETHCOL-ADC3_17") (pintype "bidirectional"))
      (node (ref "R12") (pin "2") (pinfunction "2_2") (pintype "passive"))
    )
    (net (code "17") (name "ESP_TXD") (class "Default")
      (node (ref "P3_ESP32_PROG") (pin "1") (pinfunction "1_1") (pintype "passive"))
      (node (ref "R12") (pin "1") (pinfunction "1_1") (pintype "passive"))
      (node (ref "U1") (pin "35") (pinfunction "TXD_35") (pintype "bidirectional"))
    )
    (net (code "18") (name "FB") (class "Default")
      (node (ref "R1") (pin "1") (pinfunction "1_1") (pintype "passive"))
      (node (ref "R6") (pin "2") (pinfunction "2_2") (pintype "passive"))
      (node (ref "U3") (pin "10") (pinfunction "FB_10") (pintype "passive"))
    )
    (net (code "19") (name "GND") (class "Default")
      (node (ref "C1") (pin "2") (pinfunction "2_2") (pintype "passive"))
      (node (ref "C10") (pin "2") (pinfunction "2_2") (pintype "passive"))
      (node (ref "C11") (pin "1") (pinfunction "1_1") (pintype "passive"))
      (node (ref "C12") (pin "1") (pinfunction "1_1") (pintype "passive"))
      (node (ref "C13") (pin "1") (pinfunction "1_1") (pintype "passive"))
      (node (ref "C14") (pin "1") (pinfunction "1_1") (pintype "passive"))
      (node (ref "C15") (pin "1") (pinfunction "1_1") (pintype "passive"))
      (node (ref "C16") (pin "1") (pinfunction "1_1") (pintype "passive"))
      (node (ref "C17") (pin "2") (pinfunction "2_2") (pintype "passive"))
      (node (ref "C18") (pin "2") (pinfunction "2_2") (pintype "passive"))
      (node (ref "C19") (pin "1") (pinfunction "1_1") (pintype "passive"))
      (node (ref "C20") (pin "1") (pinfunction "1_1") (pintype "passive"))
      (node (ref "C21") (pin "1") (pinfunction "1_1") (pintype "passive"))
      (node (ref "C22") (pin "1") (pinfunction "1_1") (pintype "passive"))
      (node (ref "C23") (pin "2") (pinfunction "2_2") (pintype "passive"))
      (node (ref "C24") (pin "2") (pinfunction "2_2") (pintype "passive"))
      (node (ref "C25") (pin "-") (pinfunction "-_-") (pintype "passive"))
      (node (ref "C26") (pin "-") (pinfunction "-_-") (pintype "passive"))
      (node (ref "C27") (pin "-") (pinfunction "-_-") (pintype "passive"))
      (node (ref "C28") (pin "1") (pinfunction "1_1") (pintype "passive"))
      (node (ref "C3") (pin "2") (pinfunction "2_2") (pintype "passive"))
      (node (ref "C4") (pin "2") (pinfunction "2_2") (pintype "passive"))
      (node (ref "C5") (pin "1") (pinfunction "1_1") (pintype "passive"))
      (node (ref "C6") (pin "2") (pinfunction "2_2") (pintype "passive"))
      (node (ref "C7") (pin "2") (pinfunction "2_2") (pintype "passive"))
      (node (ref "C8") (pin "1") (pinfunction "1_1") (pintype "passive"))
      (node (ref "C9") (pin "2") (pinfunction "2_2") (pintype "passive"))
      (node (ref "H5") (pin "B3,6") (pinfunction "MOUNT_B3,6") (pintype "passive"))
      (node (ref "H6") (pin "B3,6") (pinfunction "MOUNT_B3,6") (pintype "passive"))
      (node (ref "H7") (pin "B3,6") (pinfunction "MOUNT_B3,6") (pintype "passive"))
      (node (ref "H8") (pin "B3,6") (pinfunction "MOUNT_B3,6") (pintype "passive"))
      (node (ref "IC1") (pin "12") (pinfunction "VSSA_12") (pintype "power_in"))
      (node (ref "IC1") (pin "18") (pinfunction "VSS1_18") (pintype "power_in"))
      (node (ref "IC1") (pin "63") (pinfunction "VSS4_63") (pintype "bidirectional"))
      (node (ref "IC2") (pin "1") (pinfunction "ADJ_1") (pintype "input"))
      (node (ref "JP9") (pin "2") (pinfunction "2_2") (pintype "passive"))
      (node (ref "P1_LIDAR") (pin "4") (pinfunction "4_4") (pintype "passive"))
      (node (ref "P2") (pin "5") (pinfunction "5_5") (pintype "passive"))
      (node (ref "P2_ACTOR1") (pin "6") (pinfunction "6_6") (pintype "passive"))
      (node (ref "P2_ACTOR2") (pin "6") (pinfunction "6_6") (pintype "passive"))
      (node (ref "P3_ESP32_PROG") (pin "5") (pinfunction "5_5") (pintype "passive"))
      (node (ref "P4_PWRSW1") (pin "2") (pinfunction "2_2") (pintype "passive"))
      (node (ref "P4_PWRSW2") (pin "2") (pinfunction "2_2") (pintype "passive"))
      (node (ref "P5_GPS") (pin "4") (pinfunction "4_4") (pintype "passive"))
      (node (ref "Q1") (pin "2") (pinfunction "S_2") (pintype "passive"))
      (node (ref "Q4") (pin "2") (pinfunction "S_2") (pintype "passive"))
      (node (ref "Q5") (pin "2") (pinfunction "S_2") (pintype "passive"))
      (node (ref "Q6") (pin "2") (pinfunction "S_2") (pintype "passive"))
      (node (ref "Q7") (pin "2") (pinfunction "S_2") (pintype "passive"))
      (node (ref "Q8") (pin "2") (pinfunction "S_2") (pintype "passive"))
      (node (ref "R15") (pin "2") (pinfunction "2_2") (pintype "passive"))
      (node (ref "R20") (pin "1") (pinfunction "1_1") (pintype "passive"))
      (node (ref "R29") (pin "1") (pinfunction "1_1") (pintype "passive"))
      (node (ref "R39") (pin "2") (pinfunction "2_2") (pintype "passive"))
      (node (ref "R4") (pin "1") (pinfunction "1_1") (pintype "passive"))
      (node (ref "R40") (pin "2") (pinfunction "2_2") (pintype "passive"))
      (node (ref "R41") (pin "2") (pinfunction "2_2") (pintype "passive"))
      (node (ref "R42") (pin "2") (pinfunction "2_2") (pintype "passive"))
      (node (ref "R43") (pin "1") (pinfunction "1_1") (pintype "passive"))
      (node (ref "R44") (pin "1") (pinfunction "1_1") (pintype "passive"))
      (node (ref "R5") (pin "2") (pinfunction "2_2") (pintype "passive"))
      (node (ref "R6") (pin "1") (pinfunction "1_1") (pintype "passive"))
      (node (ref "SJ1") (pin "3") (pinfunction "3_3") (pintype "passive"))
      (node (ref "SJ2") (pin "3") (pinfunction "3_3") (pintype "passive"))
      (node (ref "SWD") (pin "3") (pinfunction "3_3") (pintype "passive"))
      (node (ref "T2") (pin "E") (pinfunction "E_E") (pintype "passive"))
      (node (ref "U$1") (pin "1") (pinfunction "RESV_1") (pintype "bidirectional"))
      (node (ref "U$1") (pin "18") (pinfunction "GND_18") (pintype "bidirectional"))
      (node (ref "U$1") (pin "22") (pinfunction "NCS_22") (pintype "bidirectional"))
      (node (ref "U$1") (pin "25") (pinfunction "PAD_25") (pintype "bidirectional"))
      (node (ref "U$2") (pin "5") (pinfunction "5_5") (pintype "input"))
      (node (ref "U$2") (pin "CASING1") (pinfunction "GND1_CASING1") (pintype "bidirectional"))
      (node (ref "U$2") (pin "CASING2") (pinfunction "GND2_CASING2") (pintype "bidirectional"))
      (node (ref "U$2") (pin "CASING3") (pinfunction "GND3_CASING3") (pintype "bidirectional"))
      (node (ref "U$2") (pin "CASING4") (pinfunction "GND4_CASING4") (pintype "bidirectional"))
      (node (ref "U1") (pin "1") (pinfunction "GND_1") (pintype "bidirectional"))
      (node (ref "U1") (pin "15") (pinfunction "GND_15") (pintype "bidirectional"))
      (node (ref "U1") (pin "38") (pinfunction "GND_38") (pintype "bidirectional"))
      (node (ref "U1") (pin "GND") (pinfunction "GND_GND") (pintype "bidirectional"))
      (node (ref "U2") (pin "2") (pinfunction "VSS_2") (pintype "power_in"))
      (node (ref "U3") (pin "11") (pinfunction "PAD_11") (pintype "power_in"))
      (node (ref "U3") (pin "12") (pinfunction "PAD_12") (pintype "power_in"))
      (node (ref "U3") (pin "13") (pinfunction "PAD_13") (pintype "power_in"))
      (node (ref "U3") (pin "14") (pinfunction "PAD_14") (pintype "power_in"))
      (node (ref "U3") (pin "15") (pinfunction "PAD_15") (pintype "power_in"))
      (node (ref "U3") (pin "4") (pinfunction "PGND_4") (pintype "power_in"))
      (node (ref "U3") (pin "9") (pinfunction "GND_9") (pintype "power_in"))
    )
    (net (code "20") (name "IO0") (class "Default")
      (node (ref "R13") (pin "1") (pinfunction "1_1") (pintype "passive"))
      (node (ref "T4") (pin "E") (pinfunction "E_E") (pintype "passive"))
      (node (ref "U1") (pin "25") (pinfunction "IO0_25") (pintype "bidirectional"))
    )
    (net (code "21") (name "LIDAR_PWM") (class "Default")
      (node (ref "IC1") (pin "40") (pinfunction "PC9-I2SCKIN/MCO2/TIM8CH4/SDIOD1/I2C3SDA/DCMID3/TIM3CH_40") (pintype "bidirectional"))
      (node (ref "R7") (pin "2") (pinfunction "2_2") (pintype "passive"))
    )
    (net (code "22") (name "LIDAR_RX") (class "Default")
      (node (ref "IC1") (pin "51") (pinfunction "PC10-SPI3SCK/I2S3CK/UART4TX/SDIOD2/DCMID8/USART3TX_51") (pintype "bidirectional"))
      (node (ref "R10") (pin "2") (pinfunction "2_2") (pintype "passive"))
    )
    (net (code "23") (name "LIDAR_TX") (class "Default")
      (node (ref "IC1") (pin "52") (pinfunction "PC11-UART4RX/SPI3MISO/SDIOD3/DCMID4/USART3RX/I2S3EXTSD_52") (pintype "bidirectional"))
      (node (ref "R8") (pin "2") (pinfunction "2_2") (pintype "passive"))
    )
    (net (code "24") (name "M1") (class "Default")
      (node (ref "IC1") (pin "30") (pinfunction "PB11-I2C2SDA/USART3RX/OTGD4/ETHTXEN/TIM2CH4_30") (pintype "bidirectional"))
      (node (ref "R38") (pin "1") (pinfunction "1_1") (pintype "passive"))
    )
    (net (code "25") (name "M2") (class "Default")
      (node (ref "IC1") (pin "33") (pinfunction "PB12-SPI2NSS/I2S2WS/I2C2SMBA/USART3CK/TIM1BKIN/CAN2RX/OTGD5/ETHTXD0/OTGID_33") (pintype "bidirectional"))
      (node (ref "R37") (pin "1") (pinfunction "1_1") (pintype "passive"))
    )
    (net (code "26") (name "M3") (class "Default")
      (node (ref "IC1") (pin "34") (pinfunction "PB13-SPI2SCK/I2S2CK/USART3CTS/TIM1CH1N/CAN2TX/OTGD6/ETHTXD1-OTGVBUS_34") (pintype "bidirectional"))
      (node (ref "R36") (pin "1") (pinfunction "1_1") (pintype "passive"))
    )
    (net (code "27") (name "M4") (class "Default")
      (node (ref "IC1") (pin "35") (pinfunction "PB14-SPI2MISO/TIM1CH2N/TIM12CH1/OTGDM/USART3RTS/TIM8CH3N/12S2EXTSD_35") (pintype "bidirectional"))
      (node (ref "R35") (pin "1") (pinfunction "1_1") (pintype "passive"))
    )
    (net (code "28") (name "M5") (class "Default")
      (node (ref "IC1") (pin "36") (pinfunction "PB15-SPI2MOSI/I2S2SD/TIM1CH3N/TIM8CH3N/TIM12CH2/OTGDP-RTCREFIN_36") (pintype "bidirectional"))
      (node (ref "R34") (pin "1") (pinfunction "1_1") (pintype "passive"))
    )
    (net (code "29") (name "MPU_INT") (class "Default")
      (node (ref "IC1") (pin "57") (pinfunction "PB5-I2C1SMBA/CAN2RX/OTGD7/ETHPPSOUT/TIM3CH2/SPI1MOSI/SPI3MOSI/DCMID10/I2S3SD_57") (pintype "bidirectional"))
      (node (ref "U$1") (pin "12") (pinfunction "INT_12") (pintype "bidirectional"))
    )
    (net (code "30") (name "N$10") (class "Default")
      (node (ref "IC1") (pin "8") (pinfunction "PC0-OTGSTP-ADC10_8") (pintype "bidirectional"))
      (node (ref "P2_ACTOR1") (pin "2") (pinfunction "2_2") (pintype "passive"))
    )
    (net (code "31") (name "N$36") (class "Default")
      (node (ref "IC1") (pin "9") (pinfunction "PC1-ETHMDC-ADC11_9") (pintype "bidirectional"))
      (node (ref "P2_ACTOR1") (pin "3") (pinfunction "3_3") (pintype "passive"))
    )
    (net (code "32") (name "N$37") (class "Default")
      (node (ref "IC1") (pin "10") (pinfunction "PC2-SPI2MISO/OTGDIR/ETHTXD2/I2S2EXTSD-ADC12_10") (pintype "bidirectional"))
      (node (ref "P2_ACTOR1") (pin "4") (pinfunction "4_4") (pintype "passive"))
    )
    (net (code "33") (name "N$38") (class "Default")
      (node (ref "IC1") (pin "11") (pinfunction "PC3-SPI2MOSI/I2S2SD/OTGNXT/ETHTXCLK-ADC13_11") (pintype "bidirectional"))
      (node (ref "P2_ACTOR1") (pin "5") (pinfunction "5_5") (pintype "passive"))
    )
    (net (code "34") (name "N$39") (class "Default")
      (node (ref "D5") (pin "A") (pinfunction "A_A") (pintype "passive"))
      (node (ref "P2_ACTOR2") (pin "5") (pinfunction "5_5") (pintype "passive"))
      (node (ref "U1") (pin "10") (pinfunction "IO25_10") (pintype "bidirectional"))
    )
    (net (code "35") (name "N$40") (class "Default")
      (node (ref "D3") (pin "A") (pinfunction "A_A") (pintype "passive"))
      (node (ref "P2_ACTOR2") (pin "4") (pinfunction "4_4") (pintype "passive"))
      (node (ref "U1") (pin "11") (pinfunction "IO26_11") (pintype "bidirectional"))
    )
    (net (code "36") (name "N$41") (class "Default")
      (node (ref "D2") (pin "A") (pinfunction "A_A") (pintype "passive"))
      (node (ref "P2_ACTOR2") (pin "3") (pinfunction "3_3") (pintype "passive"))
      (node (ref "U1") (pin "12") (pinfunction "IO27_12") (pintype "bidirectional"))
    )
    (net (code "37") (name "N$42") (class "Default")
      (node (ref "D1") (pin "A") (pinfunction "A_A") (pintype "passive"))
      (node (ref "P2_ACTOR2") (pin "2") (pinfunction "2_2") (pintype "passive"))
      (node (ref "U1") (pin "13") (pinfunction "IO14_13") (pintype "bidirectional"))
    )
    (net (code "38") (name "NRST") (class "Default")
      (node (ref "C14") (pin "2") (pinfunction "2_2") (pintype "passive"))
      (node (ref "IC1") (pin "7") (pinfunction "NRST_7") (pintype "bidirectional"))
      (node (ref "R16") (pin "1") (pinfunction "1_1") (pintype "passive"))
      (node (ref "SWD") (pin "5") (pinfunction "5_5") (pintype "passive"))
    )
    (net (code "39") (name "Net-(D1-PadC)") (class "Default")
      (node (ref "D1") (pin "C") (pinfunction "C_C") (pintype "passive"))
      (node (ref "R39") (pin "1") (pinfunction "1_1") (pintype "passive"))
    )
    (net (code "40") (name "Net-(D2-PadC)") (class "Default")
      (node (ref "D2") (pin "C") (pinfunction "C_C") (pintype "passive"))
      (node (ref "R40") (pin "1") (pinfunction "1_1") (pintype "passive"))
    )
    (net (code "41") (name "Net-(D3-PadC)") (class "Default")
      (node (ref "D3") (pin "C") (pinfunction "C_C") (pintype "passive"))
      (node (ref "R41") (pin "1") (pinfunction "1_1") (pintype "passive"))
    )
    (net (code "42") (name "Net-(D4-PadC)") (class "Default")
      (node (ref "D4") (pin "C") (pinfunction "C_C") (pintype "passive"))
      (node (ref "R9") (pin "2") (pinfunction "2_2") (pintype "passive"))
    )
    (net (code "43") (name "Net-(D5-PadC)") (class "Default")
      (node (ref "D5") (pin "C") (pinfunction "C_C") (pintype "passive"))
      (node (ref "R42") (pin "1") (pinfunction "1_1") (pintype "passive"))
    )
    (net (code "44") (name "Net-(D6-PadA)") (class "Default")
      (node (ref "D6") (pin "A") (pinfunction "A_A") (pintype "passive"))
      (node (ref "R43") (pin "2") (pinfunction "2_2") (pintype "passive"))
    )
    (net (code "45") (name "Net-(D7-PadA)") (class "Default")
      (node (ref "D7") (pin "A") (pinfunction "A_A") (pintype "passive"))
      (node (ref "R44") (pin "2") (pinfunction "2_2") (pintype "passive"))
    )
    (net (code "46") (name "Net-(IC1-PC6-I2S2MCK{slash}TIM8CH1{slash}SDIOD6{slash}USART6TX{slash}DCMID0{slash}TIM3CH1)") (class "Default")
      (node (ref "D6") (pin "C") (pinfunction "C_C") (pintype "passive"))
      (node (ref "IC1") (pin "37") (pinfunction "PC6-I2S2MCK/TIM8CH1/SDIOD6/USART6TX/DCMID0/TIM3CH1_37") (pintype "bidirectional"))
    )
    (net (code "47") (name "Net-(IC1-PC7-I2S3MCK{slash}TIM8CH2{slash}SDIOD7{slash}USART6RX{slash}DCMID1{slash}TIM3CH2)") (class "Default")
      (node (ref "D7") (pin "C") (pinfunction "C_C") (pintype "passive"))
      (node (ref "IC1") (pin "38") (pinfunction "PC7-I2S3MCK/TIM8CH2/SDIOD7/USART6RX/DCMID1/TIM3CH2_38") (pintype "bidirectional"))
    )
    (net (code "48") (name "Net-(IC1-PC14{slash}OSC32IN--OSC32IN)") (class "Default")
      (node (ref "C20") (pin "2") (pinfunction "2_2") (pintype "passive"))
      (node (ref "IC1") (pin "3") (pinfunction "PC14/OSC32IN--OSC32IN_3") (pintype "bidirectional"))
      (node (ref "Q3") (pin "2") (pinfunction "2_2") (pintype "passive"))
    )
    (net (code "49") (name "Net-(IC1-PC15{slash}OSC32OUT--OSC32OUT)") (class "Default")
      (node (ref "C19") (pin "2") (pinfunction "2_2") (pintype "passive"))
      (node (ref "IC1") (pin "4") (pinfunction "PC15/OSC32OUT--OSC32OUT_4") (pintype "bidirectional"))
      (node (ref "Q3") (pin "1") (pinfunction "1_1") (pintype "passive"))
    )
    (net (code "50") (name "Net-(IC1-PH0{slash}OSCIN--OSCIN)") (class "Default")
      (node (ref "C18") (pin "1") (pinfunction "1_1") (pintype "passive"))
      (node (ref "IC1") (pin "5") (pinfunction "PH0/OSCIN--OSCIN_5") (pintype "input"))
      (node (ref "Q2") (pin "2") (pinfunction "2_2") (pintype "passive"))
      (node (ref "R17") (pin "2") (pinfunction "2_2") (pintype "passive"))
    )
    (net (code "51") (name "Net-(IC1-PH1{slash}OSCOUT--OSCOUT)") (class "Default")
      (node (ref "C17") (pin "1") (pinfunction "1_1") (pintype "passive"))
      (node (ref "IC1") (pin "6") (pinfunction "PH1/OSCOUT--OSCOUT_6") (pintype "output"))
      (node (ref "Q2") (pin "1") (pinfunction "1_1") (pintype "passive"))
      (node (ref "R17") (pin "1") (pinfunction "1_1") (pintype "passive"))
    )
    (net (code "52") (name "Net-(IC1-VCAP1)") (class "Default")
      (node (ref "C6") (pin "1") (pinfunction "1_1") (pintype "passive"))
      (node (ref "IC1") (pin "31") (pinfunction "VCAP1_31") (pintype "power_in"))
    )
    (net (code "53") (name "Net-(IC1-VCAP2)") (class "Default")
      (node (ref "C7") (pin "1") (pinfunction "1_1") (pintype "passive"))
      (node (ref "IC1") (pin "47") (pinfunction "VCAP2_47") (pintype "power_in"))
    )
    (net (code "54") (name "Net-(L1-1)") (class "Default")
      (node (ref "L1") (pin "P$1") (pinfunction "1_P$1") (pintype "passive"))
      (node (ref "U3") (pin "3") (pinfunction "L_3") (pintype "passive"))
    )
    (net (code "55") (name "Net-(P2_ACTOR-Pad6)") (class "Default")
      (node (ref "P2_ACTOR") (pin "6") (pinfunction "6_6") (pintype "passive"))
      (node (ref "SJ3") (pin "2") (pinfunction "2_2") (pintype "passive"))
    )
    (net (code "56") (name "Net-(P5_GPS-Pad2)") (class "Default")
      (node (ref "P5_GPS") (pin "2") (pinfunction "2_2") (pintype "passive"))
      (node (ref "R10") (pin "1") (pinfunction "1_1") (pintype "passive"))
    )
    (net (code "57") (name "Net-(P5_GPS-Pad3)") (class "Default")
      (node (ref "P5_GPS") (pin "3") (pinfunction "3_3") (pintype "passive"))
      (node (ref "R8") (pin "1") (pinfunction "1_1") (pintype "passive"))
    )
    (net (code "58") (name "Net-(Q1-D)") (class "Default")
      (node (ref "P4_LIDAR_MOTOR") (pin "2") (pinfunction "2_2") (pintype "passive"))
      (node (ref "Q1") (pin "3") (pinfunction "D_3") (pintype "passive"))
    )
    (net (code "59") (name "Net-(Q1-G)") (class "Default")
      (node (ref "Q1") (pin "1") (pinfunction "G_1") (pintype "passive"))
      (node (ref "R7") (pin "1") (pinfunction "1_1") (pintype "passive"))
    )
    (net (code "60") (name "Net-(Q4-D)") (class "Default")
      (node (ref "P2_ACTOR") (pin "5") (pinfunction "5_5") (pintype "passive"))
      (node (ref "Q4") (pin "3") (pinfunction "D_3") (pintype "passive"))
    )
    (net (code "61") (name "Net-(Q4-G)") (class "Default")
      (node (ref "Q4") (pin "1") (pinfunction "G_1") (pintype "passive"))
      (node (ref "R34") (pin "2") (pinfunction "2_2") (pintype "passive"))
    )
    (net (code "62") (name "Net-(Q5-D)") (class "Default")
      (node (ref "P2_ACTOR") (pin "4") (pinfunction "4_4") (pintype "passive"))
      (node (ref "Q5") (pin "3") (pinfunction "D_3") (pintype "passive"))
    )
    (net (code "63") (name "Net-(Q5-G)") (class "Default")
      (node (ref "Q5") (pin "1") (pinfunction "G_1") (pintype "passive"))
      (node (ref "R35") (pin "2") (pinfunction "2_2") (pintype "passive"))
    )
    (net (code "64") (name "Net-(Q6-D)") (class "Default")
      (node (ref "P2_ACTOR") (pin "3") (pinfunction "3_3") (pintype "passive"))
      (node (ref "Q6") (pin "3") (pinfunction "D_3") (pintype "passive"))
    )
    (net (code "65") (name "Net-(Q6-G)") (class "Default")
      (node (ref "Q6") (pin "1") (pinfunction "G_1") (pintype "passive"))
      (node (ref "R36") (pin "2") (pinfunction "2_2") (pintype "passive"))
    )
    (net (code "66") (name "Net-(Q7-D)") (class "Default")
      (node (ref "P2_ACTOR") (pin "2") (pinfunction "2_2") (pintype "passive"))
      (node (ref "Q7") (pin "3") (pinfunction "D_3") (pintype "passive"))
    )
    (net (code "67") (name "Net-(Q7-G)") (class "Default")
      (node (ref "Q7") (pin "1") (pinfunction "G_1") (pintype "passive"))
      (node (ref "R37") (pin "2") (pinfunction "2_2") (pintype "passive"))
    )
    (net (code "68") (name "Net-(Q8-D)") (class "Default")
      (node (ref "P2_ACTOR") (pin "1") (pinfunction "1_1") (pintype "passive"))
      (node (ref "Q8") (pin "3") (pinfunction "D_3") (pintype "passive"))
    )
    (net (code "69") (name "Net-(Q8-G)") (class "Default")
      (node (ref "Q8") (pin "1") (pinfunction "G_1") (pintype "passive"))
      (node (ref "R38") (pin "2") (pinfunction "2_2") (pintype "passive"))
    )
    (net (code "70") (name "Net-(R20-Pad2)") (class "Default")
      (node (ref "R20") (pin "2") (pinfunction "2_2") (pintype "passive"))
      (node (ref "R23") (pin "1") (pinfunction "1_1") (pintype "passive"))
      (node (ref "T1") (pin "B") (pinfunction "B_B") (pintype "passive"))
      (node (ref "T2") (pin "C") (pinfunction "C_C") (pintype "passive"))
    )
    (net (code "71") (name "Net-(R21-Pad1)") (class "Default")
      (node (ref "R21") (pin "1") (pinfunction "1_1") (pintype "passive"))
      (node (ref "SJ1") (pin "2") (pinfunction "2_2") (pintype "passive"))
    )
    (net (code "72") (name "Net-(R22-Pad1)") (class "Default")
      (node (ref "R22") (pin "1") (pinfunction "1_1") (pintype "passive"))
      (node (ref "SJ2") (pin "2") (pinfunction "2_2") (pintype "passive"))
    )
    (net (code "73") (name "Net-(R23-Pad2)") (class "Default")
      (node (ref "R23") (pin "2") (pinfunction "2_2") (pintype "passive"))
      (node (ref "R24") (pin "1") (pinfunction "1_1") (pintype "passive"))
    )
    (net (code "74") (name "Net-(R25-Pad2)") (class "Default")
      (node (ref "R25") (pin "2") (pinfunction "2_2") (pintype "passive"))
      (node (ref "T1") (pin "E") (pinfunction "E_E") (pintype "passive"))
    )
    (net (code "75") (name "Net-(R26-Pad1)") (class "Default")
      (node (ref "R26") (pin "1") (pinfunction "1_1") (pintype "passive"))
      (node (ref "R27") (pin "2") (pinfunction "2_2") (pintype "passive"))
      (node (ref "T2") (pin "B") (pinfunction "B_B") (pintype "passive"))
    )
    (net (code "76") (name "Net-(R30-Pad2)") (class "Default")
      (node (ref "R30") (pin "2") (pinfunction "2_2") (pintype "passive"))
      (node (ref "T3") (pin "B") (pinfunction "B_B") (pintype "passive"))
    )
    (net (code "77") (name "Net-(R31-Pad2)") (class "Default")
      (node (ref "R31") (pin "2") (pinfunction "2_2") (pintype "passive"))
      (node (ref "T4") (pin "B") (pinfunction "B_B") (pintype "passive"))
    )
    (net (code "78") (name "Net-(U$1-REGOUT)") (class "Default")
      (node (ref "C23") (pin "1") (pinfunction "1_1") (pintype "passive"))
      (node (ref "U$1") (pin "10") (pinfunction "REGOUT_10") (pintype "bidirectional"))
    )
    (net (code "79") (name "Net-(U$1-RESV2)") (class "Default")
      (node (ref "C28") (pin "2") (pinfunction "2_2") (pintype "passive"))
      (node (ref "U$1") (pin "20") (pinfunction "RESV2_20") (pintype "bidirectional"))
    )
    (net (code "80") (name "Net-(U1-IO2)") (class "Default")
      (node (ref "R15") (pin "1") (pinfunction "1_1") (pintype "passive"))
      (node (ref "U1") (pin "24") (pinfunction "IO2_24") (pintype "bidirectional"))
    )
    (net (code "81") (name "Net-(U2-PROG)") (class "Default")
      (node (ref "R5") (pin "1") (pinfunction "1_1") (pintype "passive"))
      (node (ref "U2") (pin "5") (pinfunction "PROG_5") (pintype "input"))
    )
    (net (code "82") (name "Net-(U2-STAT)") (class "Default")
      (node (ref "R9") (pin "1") (pinfunction "1_1") (pintype "passive"))
      (node (ref "U2") (pin "1") (pinfunction "STAT_1") (pintype "output"))
    )
    (net (code "83") (name "Net-(U3-UVLO)") (class "Default")
      (node (ref "C2") (pin "2") (pinfunction "2_2") (pintype "passive"))
      (node (ref "R3") (pin "1") (pinfunction "1_1") (pintype "passive"))
      (node (ref "R4") (pin "2") (pinfunction "2_2") (pintype "passive"))
      (node (ref "U3") (pin "7") (pinfunction "UVLO_7") (pintype "passive"))
    )
    (net (code "84") (name "Net-(U3-VAUX)") (class "Default")
      (node (ref "C4") (pin "1") (pinfunction "1_1") (pintype "passive"))
      (node (ref "U3") (pin "1") (pinfunction "VAUX_1") (pintype "passive"))
    )
    (net (code "85") (name "SCL") (class "Default")
      (node (ref "IC1") (pin "58") (pinfunction "PB6-I2C1SCL/TIM4CH1/CAN2TX/DCMID5/USART1TX_58") (pintype "bidirectional"))
      (node (ref "P2") (pin "3") (pinfunction "3_3") (pintype "passive"))
      (node (ref "R32") (pin "2") (pinfunction "2_2") (pintype "passive"))
      (node (ref "U$1") (pin "23") (pinfunction "SCL/SCLK_23") (pintype "bidirectional"))
    )
    (net (code "86") (name "SDA") (class "Default")
      (node (ref "IC1") (pin "59") (pinfunction "PB7-I2C1SDA/FSMCNL/DCMIVSYNC/USART1RX/TIM4CH2_59") (pintype "bidirectional"))
      (node (ref "P2") (pin "4") (pinfunction "4_4") (pintype "passive"))
      (node (ref "R33") (pin "2") (pinfunction "2_2") (pintype "passive"))
      (node (ref "U$1") (pin "24") (pinfunction "SDA/SDI_24") (pintype "bidirectional"))
    )
    (net (code "87") (name "SWCLK") (class "Default")
      (node (ref "IC1") (pin "49") (pinfunction "PA14/JTCK/SWCLK_49") (pintype "bidirectional"))
      (node (ref "SWD") (pin "2") (pinfunction "2_2") (pintype "passive"))
    )
    (net (code "88") (name "SWDIO") (class "Default")
      (node (ref "IC1") (pin "46") (pinfunction "PA13/JTMS/SWDIO_46") (pintype "bidirectional"))
      (node (ref "SWD") (pin "4") (pinfunction "4_4") (pintype "passive"))
    )
    (net (code "89") (name "TRACESWO") (class "Default")
      (node (ref "IC1") (pin "55") (pinfunction "PB3/JTDO/TRACESWO-SPI3SCK/I2S3CK/TIM2CH2/SPI1SCK_55") (pintype "bidirectional"))
      (node (ref "SWD") (pin "6") (pinfunction "6_6") (pintype "passive"))
    )
    (net (code "90") (name "UART1_RX") (class "Default")
      (node (ref "IC1") (pin "43") (pinfunction "PA10-USART1RX/TIM1CH3/OTGFSID/DCMID1_43") (pintype "bidirectional"))
      (node (ref "P1_LIDAR") (pin "3") (pinfunction "3_3") (pintype "passive"))
    )
    (net (code "91") (name "UART1_TX") (class "Default")
      (node (ref "IC1") (pin "42") (pinfunction "PA9-USART1TX/TIM1CH2/I2C3SMBA/DCMID0-OTGFSVBUS_42") (pintype "bidirectional"))
      (node (ref "P1_LIDAR") (pin "2") (pinfunction "2_2") (pintype "passive"))
    )
    (net (code "92") (name "USBP_E") (class "Default")
      (node (ref "IC1") (pin "24") (pinfunction "PC4-ETHRXD0-ADC14_24") (pintype "bidirectional"))
      (node (ref "R28") (pin "1") (pinfunction "1_1") (pintype "passive"))
      (node (ref "R29") (pin "2") (pinfunction "2_2") (pintype "passive"))
    )
    (net (code "93") (name "USB_D+") (class "Default")
      (node (ref "IC1") (pin "45") (pinfunction "PA12-USART1RTS/CAN1TX/TIM1ETR/OTGFSDP_45") (pintype "bidirectional"))
      (node (ref "R18") (pin "2") (pinfunction "2_2") (pintype "passive"))
      (node (ref "R25") (pin "1") (pinfunction "1_1") (pintype "passive"))
    )
    (net (code "94") (name "USB_D-") (class "Default")
      (node (ref "IC1") (pin "44") (pinfunction "PA11-USART1CTS/CAN1RX/TIM1CH4/OTGFSDM_44") (pintype "bidirectional"))
      (node (ref "R19") (pin "2") (pinfunction "2_2") (pintype "passive"))
    )
    (net (code "95") (name "VBATT") (class "Default")
      (node (ref "C1") (pin "1") (pinfunction "1_1") (pintype "passive"))
      (node (ref "C10") (pin "1") (pinfunction "1_1") (pintype "passive"))
      (node (ref "C2") (pin "1") (pinfunction "1_1") (pintype "passive"))
      (node (ref "L1") (pin "P$2") (pinfunction "2_P$2") (pintype "passive"))
      (node (ref "P4_PWRSW2") (pin "1") (pinfunction "1_1") (pintype "passive"))
      (node (ref "R2") (pin "1") (pinfunction "1_1") (pintype "passive"))
      (node (ref "R3") (pin "2") (pinfunction "2_2") (pintype "passive"))
      (node (ref "U2") (pin "3") (pinfunction "VBAT_3") (pintype "power_in"))
      (node (ref "U3") (pin "5") (pinfunction "VIN_5") (pintype "power_in"))
    )
    (net (code "96") (name "VBUS") (class "Default")
      (node (ref "F1") (pin "2") (pinfunction "2_2") (pintype "passive"))
      (node (ref "U$2") (pin "1") (pinfunction "1_1") (pintype "input"))
    )
    (net (code "97") (name "unconnected-(IC1-PA4-SPI1NSS{slash}SPI3NSS{slash}USART2CK{slash}DCMIHSYNC{slash}OTGSOF{slash}I2S3WS-ADC4{slash}DAC1-Pad20)") (class "Default")
      (node (ref "IC1") (pin "20") (pinfunction "PA4-SPI1NSS/SPI3NSS/USART2CK/DCMIHSYNC/OTGSOF/I2S3WS-ADC4/DAC1_20") (pintype "bidirectional"))
    )
    (net (code "98") (name "unconnected-(IC1-PA5-SPI1SCK{slash}OTGCK{slash}TIM2CH1ETR{slash}TIM8CH1N-ADC5{slash}DAC2-Pad21)") (class "Default")
      (node (ref "IC1") (pin "21") (pinfunction "PA5-SPI1SCK/OTGCK/TIM2CH1ETR/TIM8CH1N-ADC5/DAC2_21") (pintype "bidirectional"))
    )
    (net (code "99") (name "unconnected-(IC1-PA6-SPI1MISO{slash}TIM8BKIN{slash}TIM13CH1{slash}DCMIPIXCLK{slash}TIM3CH1{slash}TIM1BKIN-ADC6-Pad22)") (class "Default")
      (node (ref "IC1") (pin "22") (pinfunction "PA6-SPI1MISO/TIM8BKIN/TIM13CH1/DCMIPIXCLK/TIM3CH1/TIM1BKIN-ADC6_22") (pintype "bidirectional"))
    )
    (net (code "100") (name "unconnected-(IC1-PA7-SPI1MOSI{slash}TIM8CH1N{slash}TIM14CH1{slash}TIM3CH2{slash}ETHRXDV{slash}TIM1CH1N{slash}ETHCRSDV-ADC7-Pad23)") (class "Default")
      (node (ref "IC1") (pin "23") (pinfunction "PA7-SPI1MOSI/TIM8CH1N/TIM14CH1/TIM3CH2/ETHRXDV/TIM1CH1N/ETHCRSDV-ADC7_23") (pintype "bidirectional"))
    )
    (net (code "101") (name "unconnected-(IC1-PA8-MCO1{slash}USART1CK{slash}TIM1CH1{slash}I2C3SCL{slash}OTGSOF-Pad41)") (class "Default")
      (node (ref "IC1") (pin "41") (pinfunction "PA8-MCO1/USART1CK/TIM1CH1/I2C3SCL/OTGSOF_41") (pintype "bidirectional"))
    )
    (net (code "102") (name "unconnected-(IC1-PA15{slash}JTDI-SPI3NSS{slash}I2S3WS{slash}TIM2CH1ETR{slash}SPI1NSS-Pad50)") (class "Default")
      (node (ref "IC1") (pin "50") (pinfunction "PA15/JTDI-SPI3NSS/I2S3WS/TIM2CH1ETR/SPI1NSS_50") (pintype "bidirectional"))
    )
    (net (code "103") (name "unconnected-(IC1-PB0-TIM3CH3{slash}TIM8CH2N{slash}OTGD1{slash}ETHRXD2{slash}TIM2CH2N-ADC8-Pad26)") (class "Default")
      (node (ref "IC1") (pin "26") (pinfunction "PB0-TIM3CH3/TIM8CH2N/OTGD1/ETHRXD2/TIM2CH2N-ADC8_26") (pintype "bidirectional"))
    )
    (net (code "104") (name "unconnected-(IC1-PB2-TIM3CH4{slash}TIM8CH3N{slash}OTGD2{slash}ETHRXD3{slash}TIM1CH3N-ADC9-Pad27)") (class "Default")
      (node (ref "IC1") (pin "27") (pinfunction "PB2-TIM3CH4/TIM8CH3N/OTGD2/ETHRXD3/TIM1CH3N-ADC9_27") (pintype "bidirectional"))
    )
    (net (code "105") (name "unconnected-(IC1-PB4{slash}JNTRST-SPI3MISO{slash}TIM3CH1{slash}SPI1MISO{slash}I2S3EXTSD-Pad56)") (class "Default")
      (node (ref "IC1") (pin "56") (pinfunction "PB4/JNTRST-SPI3MISO/TIM3CH1/SPI1MISO/I2S3EXTSD_56") (pintype "bidirectional"))
    )
    (net (code "106") (name "unconnected-(IC1-PB8-TIM4CH3{slash}SDIOD4{slash}TIM10CH1{slash}DCMID6{slash}ETHTXD3{slash}I2C1SCL{slash}CAN1RX-Pad61)") (class "Default")
      (node (ref "IC1") (pin "61") (pinfunction "PB8-TIM4CH3/SDIOD4/TIM10CH1/DCMID6/ETHTXD3/I2C1SCL/CAN1RX_61") (pintype "bidirectional"))
    )
    (net (code "107") (name "unconnected-(IC1-PB9-SPI2NSS{slash}I2S2WS{slash}TIM4CH4{slash}TIM11CH1{slash}SDIOD5{slash}DCMID7{slash}I2C1SDA{slash}CAN1TX-Pad62)") (class "Default")
      (node (ref "IC1") (pin "62") (pinfunction "PB9-SPI2NSS/I2S2WS/TIM4CH4/TIM11CH1/SDIOD5/DCMID7/I2C1SDA/CAN1TX_62") (pintype "bidirectional"))
    )
    (net (code "108") (name "unconnected-(IC1-PB10-SPI2SCK{slash}I2S2CK{slash}I2C2SCL{slash}USART3TX{slash}OTGD3{slash}ETHRXER{slash}TIM2CH3-Pad29)") (class "Default")
      (node (ref "IC1") (pin "29") (pinfunction "PB10-SPI2SCK/I2S2CK/I2C2SCL/USART3TX/OTGD3/ETHRXER/TIM2CH3_29") (pintype "bidirectional"))
    )
    (net (code "109") (name "unconnected-(IC1-PC8-TIM8CH3{slash}SDIOD0{slash}TIM3CH3{slash}USART6CK{slash}DCMID2-Pad39)") (class "Default")
      (node (ref "IC1") (pin "39") (pinfunction "PC8-TIM8CH3/SDIOD0/TIM3CH3/USART6CK/DCMID2_39") (pintype "bidirectional"))
    )
    (net (code "110") (name "unconnected-(IC1-PC12-UART5TX{slash}SDIOCK{slash}DCMID9{slash}SPI3MOSI{slash}I2S3SD{slash}USART3CK-Pad53)") (class "Default")
      (node (ref "IC1") (pin "53") (pinfunction "PC12-UART5TX/SDIOCK/DCMID9/SPI3MOSI/I2S3SD/USART3CK_53") (pintype "bidirectional"))
    )
    (net (code "111") (name "unconnected-(IC1-PC13--RTCO{slash}RTCTAMP1{slash}RTCTS-Pad2)") (class "Default")
      (node (ref "IC1") (pin "2") (pinfunction "PC13--RTCO/RTCTAMP1/RTCTS_2") (pintype "bidirectional"))
    )
    (net (code "112") (name "unconnected-(U$1-ADO{slash}SDO-Pad9)") (class "Default")
      (node (ref "U$1") (pin "9") (pinfunction "ADO/SDO_9") (pintype "bidirectional"))
    )
    (net (code "113") (name "unconnected-(U$1-AUX_CL-Pad7)") (class "Default")
      (node (ref "U$1") (pin "7") (pinfunction "AUX_CL_7") (pintype "bidirectional"))
    )
    (net (code "114") (name "unconnected-(U$1-AUX_DA-Pad21)") (class "Default")
      (node (ref "U$1") (pin "21") (pinfunction "AUX_DA_21") (pintype "bidirectional"))
    )
    (net (code "115") (name "unconnected-(U$1-FSYNC-Pad11)") (class "Default")
      (node (ref "U$1") (pin "11") (pinfunction "FSYNC_11") (pintype "bidirectional"))
    )
    (net (code "116") (name "unconnected-(U$1-NC1-Pad2)") (class "Default")
      (node (ref "U$1") (pin "2") (pinfunction "NC1_2") (pintype "bidirectional"))
    )
    (net (code "117") (name "unconnected-(U$1-NC2-Pad3)") (class "Default")
      (node (ref "U$1") (pin "3") (pinfunction "NC2_3") (pintype "bidirectional"))
    )
    (net (code "118") (name "unconnected-(U$1-NC3-Pad4)") (class "Default")
      (node (ref "U$1") (pin "4") (pinfunction "NC3_4") (pintype "bidirectional"))
    )
    (net (code "119") (name "unconnected-(U$1-NC4-Pad5)") (class "Default")
      (node (ref "U$1") (pin "5") (pinfunction "NC4_5") (pintype "bidirectional"))
    )
    (net (code "120") (name "unconnected-(U$1-NC5-Pad6)") (class "Default")
      (node (ref "U$1") (pin "6") (pinfunction "NC5_6") (pintype "bidirectional"))
    )
    (net (code "121") (name "unconnected-(U$1-NC6-Pad14)") (class "Default")
      (node (ref "U$1") (pin "14") (pinfunction "NC6_14") (pintype "bidirectional"))
    )
    (net (code "122") (name "unconnected-(U$1-NC7-Pad15)") (class "Default")
      (node (ref "U$1") (pin "15") (pinfunction "NC7_15") (pintype "bidirectional"))
    )
    (net (code "123") (name "unconnected-(U$1-NC8-Pad16)") (class "Default")
      (node (ref "U$1") (pin "16") (pinfunction "NC8_16") (pintype "bidirectional"))
    )
    (net (code "124") (name "unconnected-(U$1-NC9-Pad17)") (class "Default")
      (node (ref "U$1") (pin "17") (pinfunction "NC9_17") (pintype "bidirectional"))
    )
    (net (code "125") (name "unconnected-(U$1-RESV1-Pad19)") (class "Default")
      (node (ref "U$1") (pin "19") (pinfunction "RESV1_19") (pintype "bidirectional"))
    )
    (net (code "126") (name "unconnected-(U$2-Pad4)") (class "Default")
      (node (ref "U$2") (pin "4") (pinfunction "4_4") (pintype "input"))
    )
    (net (code "127") (name "unconnected-(U1-IO4-Pad26)") (class "Default")
      (node (ref "U1") (pin "26") (pinfunction "IO4_26") (pintype "bidirectional"))
    )
    (net (code "128") (name "unconnected-(U1-IO5-Pad29)") (class "Default")
      (node (ref "U1") (pin "29") (pinfunction "IO5_29") (pintype "bidirectional"))
    )
    (net (code "129") (name "unconnected-(U1-IO12-Pad14)") (class "Default")
      (node (ref "U1") (pin "14") (pinfunction "IO12_14") (pintype "bidirectional"))
    )
    (net (code "130") (name "unconnected-(U1-IO13-Pad16)") (class "Default")
      (node (ref "U1") (pin "16") (pinfunction "IO13_16") (pintype "bidirectional"))
    )
    (net (code "131") (name "unconnected-(U1-IO15-Pad23)") (class "Default")
      (node (ref "U1") (pin "23") (pinfunction "IO15_23") (pintype "bidirectional"))
    )
    (net (code "132") (name "unconnected-(U1-IO16-Pad27)") (class "Default")
      (node (ref "U1") (pin "27") (pinfunction "IO16_27") (pintype "bidirectional"))
    )
    (net (code "133") (name "unconnected-(U1-IO17-Pad28)") (class "Default")
      (node (ref "U1") (pin "28") (pinfunction "IO17_28") (pintype "bidirectional"))
    )
    (net (code "134") (name "unconnected-(U1-IO18-Pad30)") (class "Default")
      (node (ref "U1") (pin "30") (pinfunction "IO18_30") (pintype "bidirectional"))
    )
    (net (code "135") (name "unconnected-(U1-IO19-Pad31)") (class "Default")
      (node (ref "U1") (pin "31") (pinfunction "IO19_31") (pintype "bidirectional"))
    )
    (net (code "136") (name "unconnected-(U1-IO21-Pad33)") (class "Default")
      (node (ref "U1") (pin "33") (pinfunction "IO21_33") (pintype "bidirectional"))
    )
    (net (code "137") (name "unconnected-(U1-IO22-Pad36)") (class "Default")
      (node (ref "U1") (pin "36") (pinfunction "IO22_36") (pintype "bidirectional"))
    )
    (net (code "138") (name "unconnected-(U1-IO23-Pad37)") (class "Default")
      (node (ref "U1") (pin "37") (pinfunction "IO23_37") (pintype "bidirectional"))
    )
    (net (code "139") (name "unconnected-(U1-IO32-Pad8)") (class "Default")
      (node (ref "U1") (pin "8") (pinfunction "IO32_8") (pintype "bidirectional"))
    )
    (net (code "140") (name "unconnected-(U1-IO33-Pad9)") (class "Default")
      (node (ref "U1") (pin "9") (pinfunction "IO33_9") (pintype "bidirectional"))
    )
    (net (code "141") (name "unconnected-(U1-IO34-Pad6)") (class "Default")
      (node (ref "U1") (pin "6") (pinfunction "IO34_6") (pintype "bidirectional"))
    )
    (net (code "142") (name "unconnected-(U1-IO35-Pad7)") (class "Default")
      (node (ref "U1") (pin "7") (pinfunction "IO35_7") (pintype "bidirectional"))
    )
    (net (code "143") (name "unconnected-(U1-SCK-Pad20)") (class "Default")
      (node (ref "U1") (pin "20") (pinfunction "SCK_20") (pintype "bidirectional"))
    )
    (net (code "144") (name "unconnected-(U1-SCS-Pad19)") (class "Default")
      (node (ref "U1") (pin "19") (pinfunction "SCS_19") (pintype "bidirectional"))
    )
    (net (code "145") (name "unconnected-(U1-SDI-Pad22)") (class "Default")
      (node (ref "U1") (pin "22") (pinfunction "SDI_22") (pintype "bidirectional"))
    )
    (net (code "146") (name "unconnected-(U1-SDO-Pad21)") (class "Default")
      (node (ref "U1") (pin "21") (pinfunction "SDO_21") (pintype "bidirectional"))
    )
    (net (code "147") (name "unconnected-(U1-SENSOR_VN-Pad5)") (class "Default")
      (node (ref "U1") (pin "5") (pinfunction "SENSOR_VN_5") (pintype "bidirectional"))
    )
    (net (code "148") (name "unconnected-(U1-SENSOR_VP-Pad4)") (class "Default")
      (node (ref "U1") (pin "4") (pinfunction "SENSOR_VP_4") (pintype "bidirectional"))
    )
    (net (code "149") (name "unconnected-(U1-SHD-Pad17)") (class "Default")
      (node (ref "U1") (pin "17") (pinfunction "SHD_17") (pintype "bidirectional"))
    )
    (net (code "150") (name "unconnected-(U1-SWP-Pad18)") (class "Default")
      (node (ref "U1") (pin "18") (pinfunction "SWP_18") (pintype "bidirectional"))
    )
  )
)
